# canSlaveV02_8s.net
KiCad netlist of a schematic drawn in EAGLE
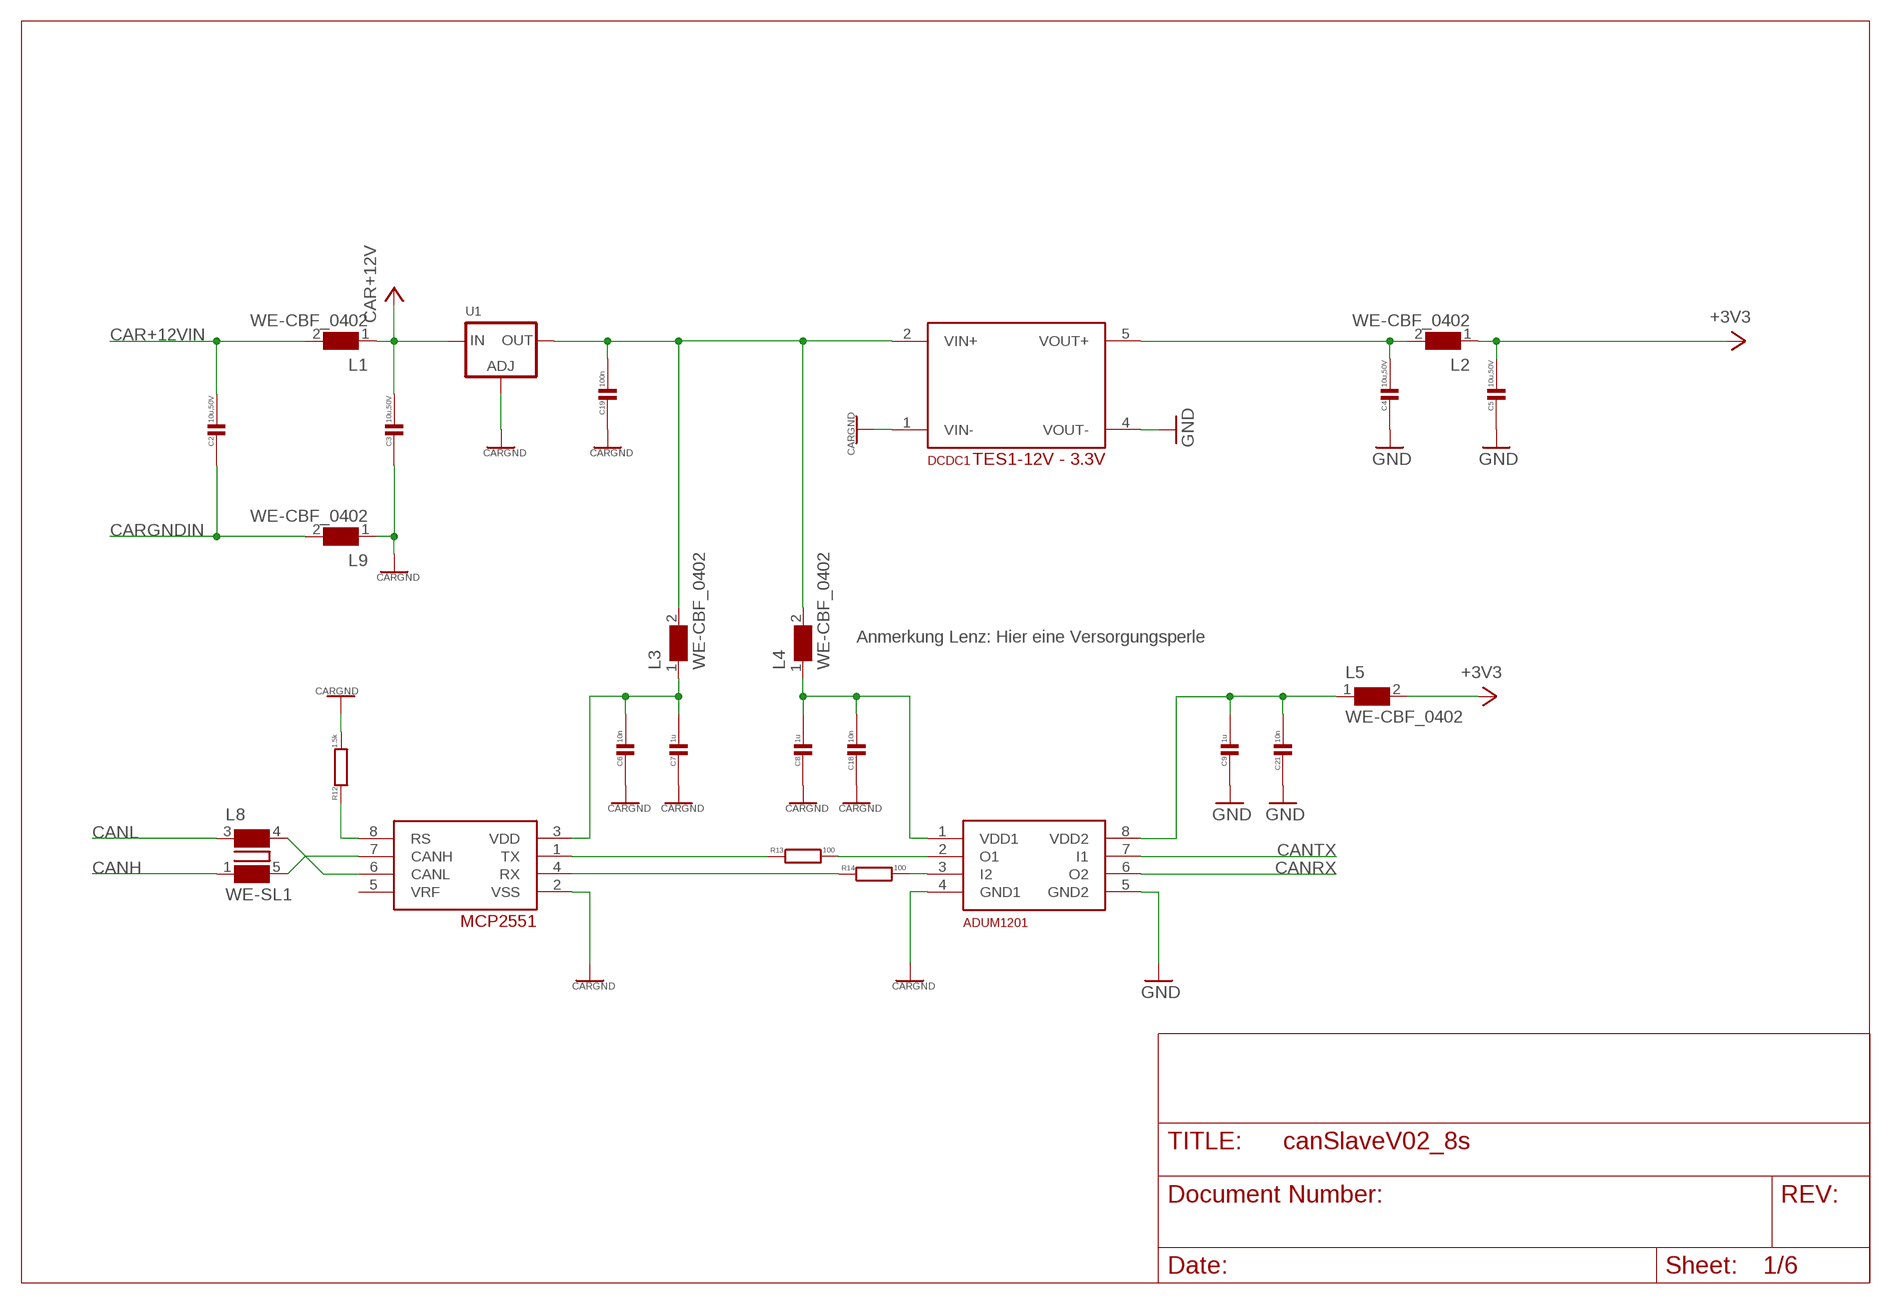
[diagram p0: schematic, sheet 1]
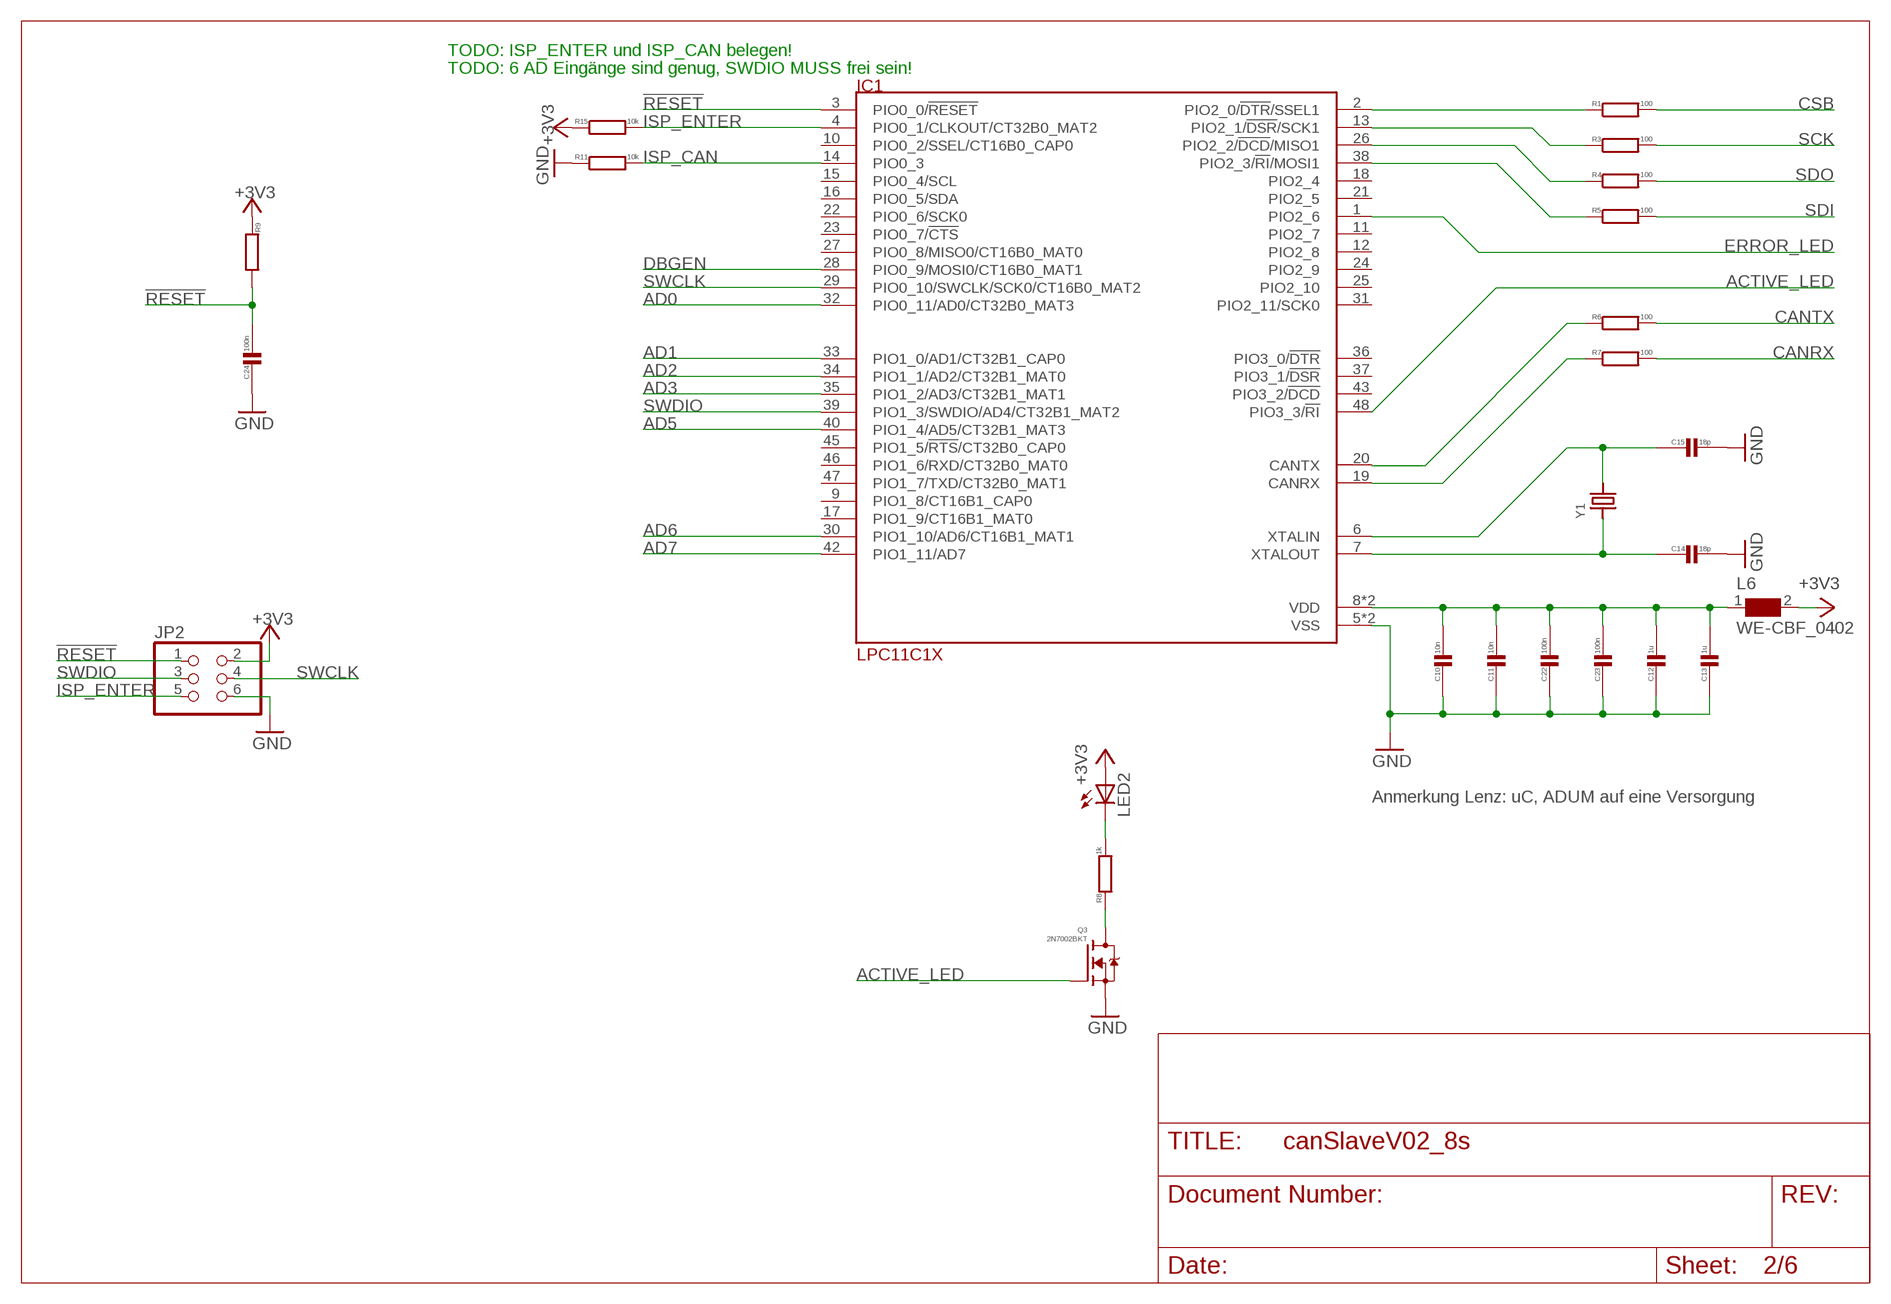
[diagram p1: schematic, sheet 2]
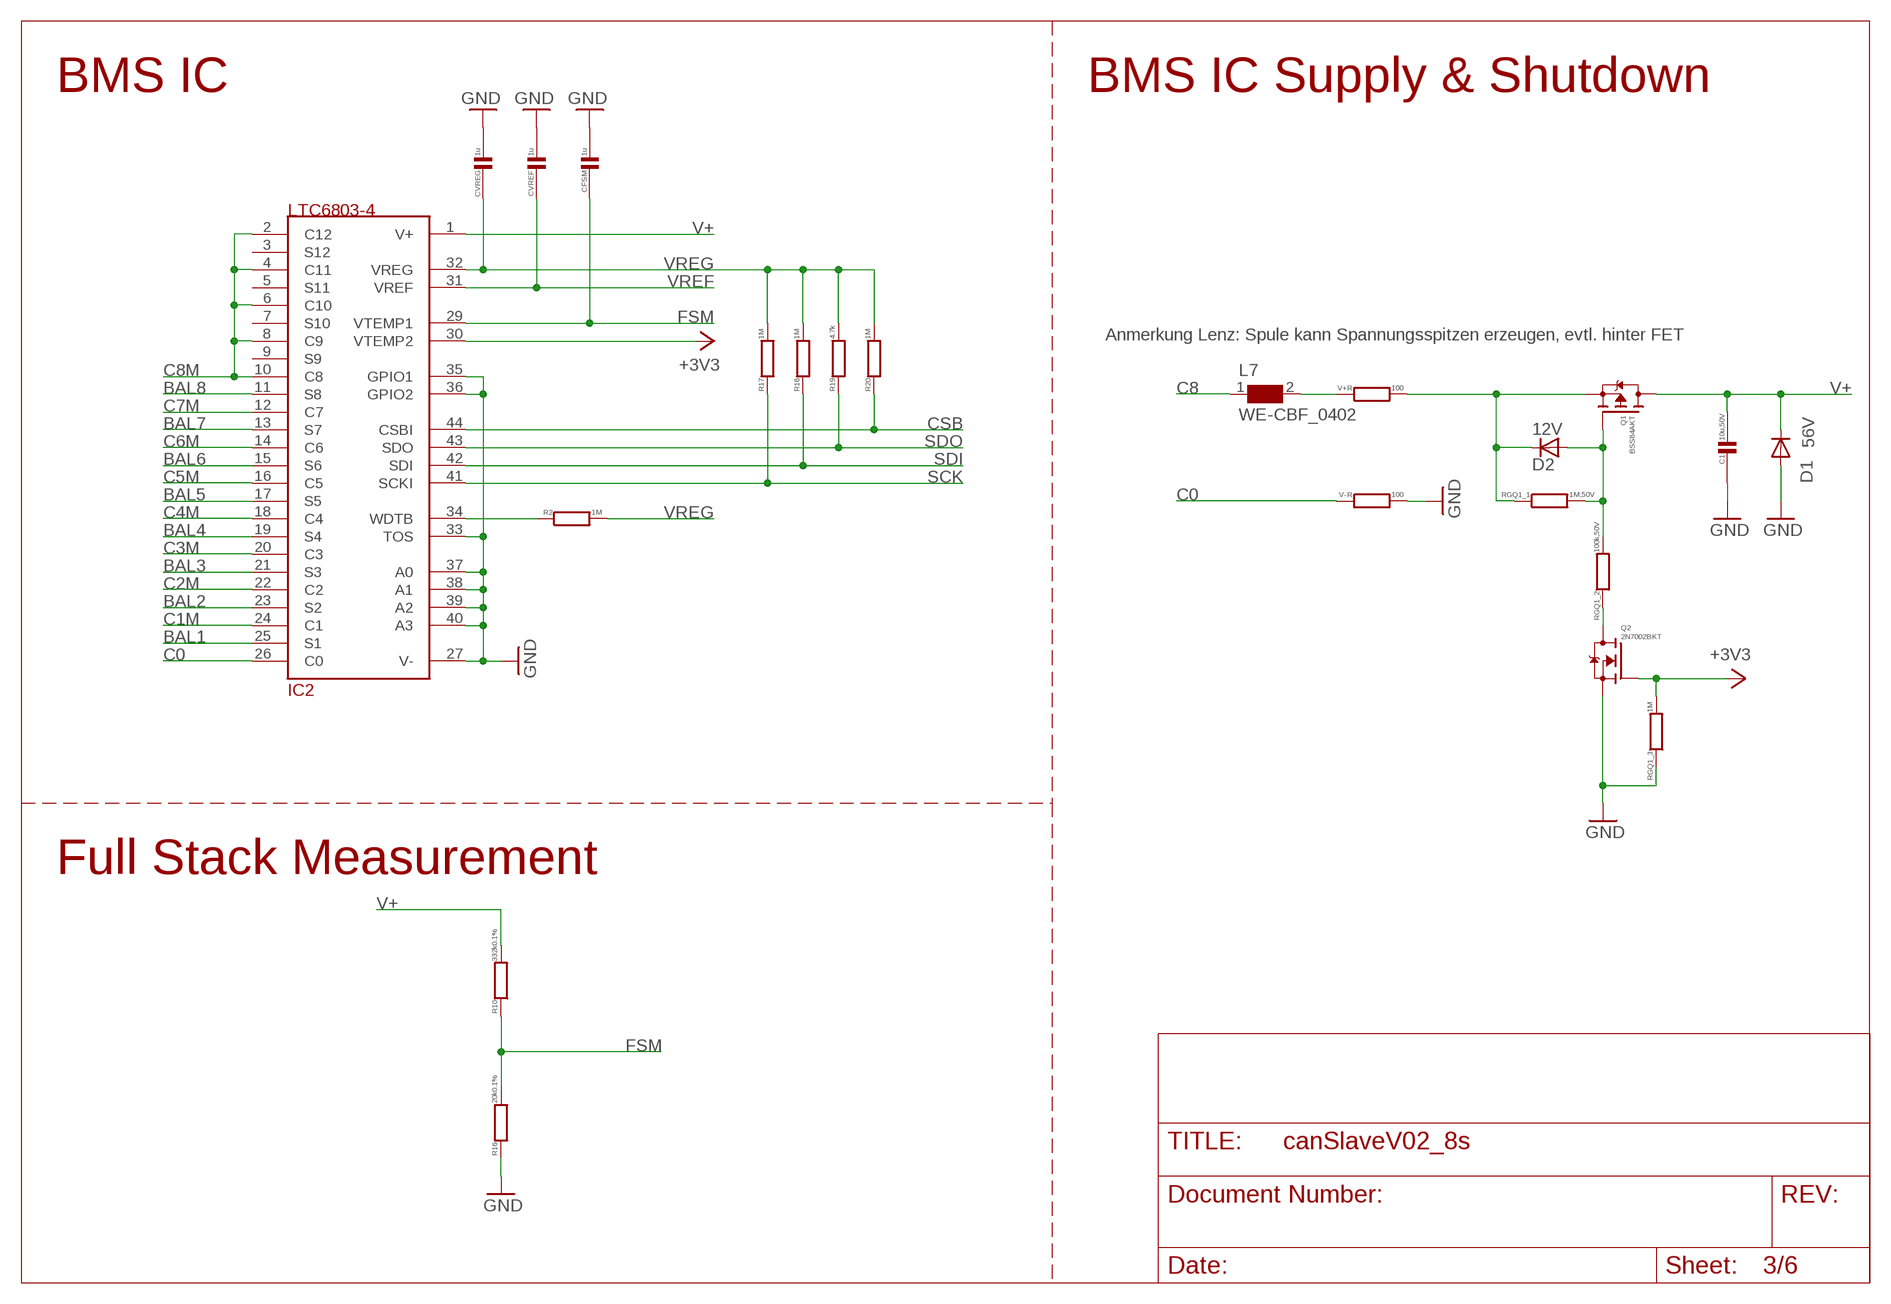
[diagram p2: schematic, sheet 3]
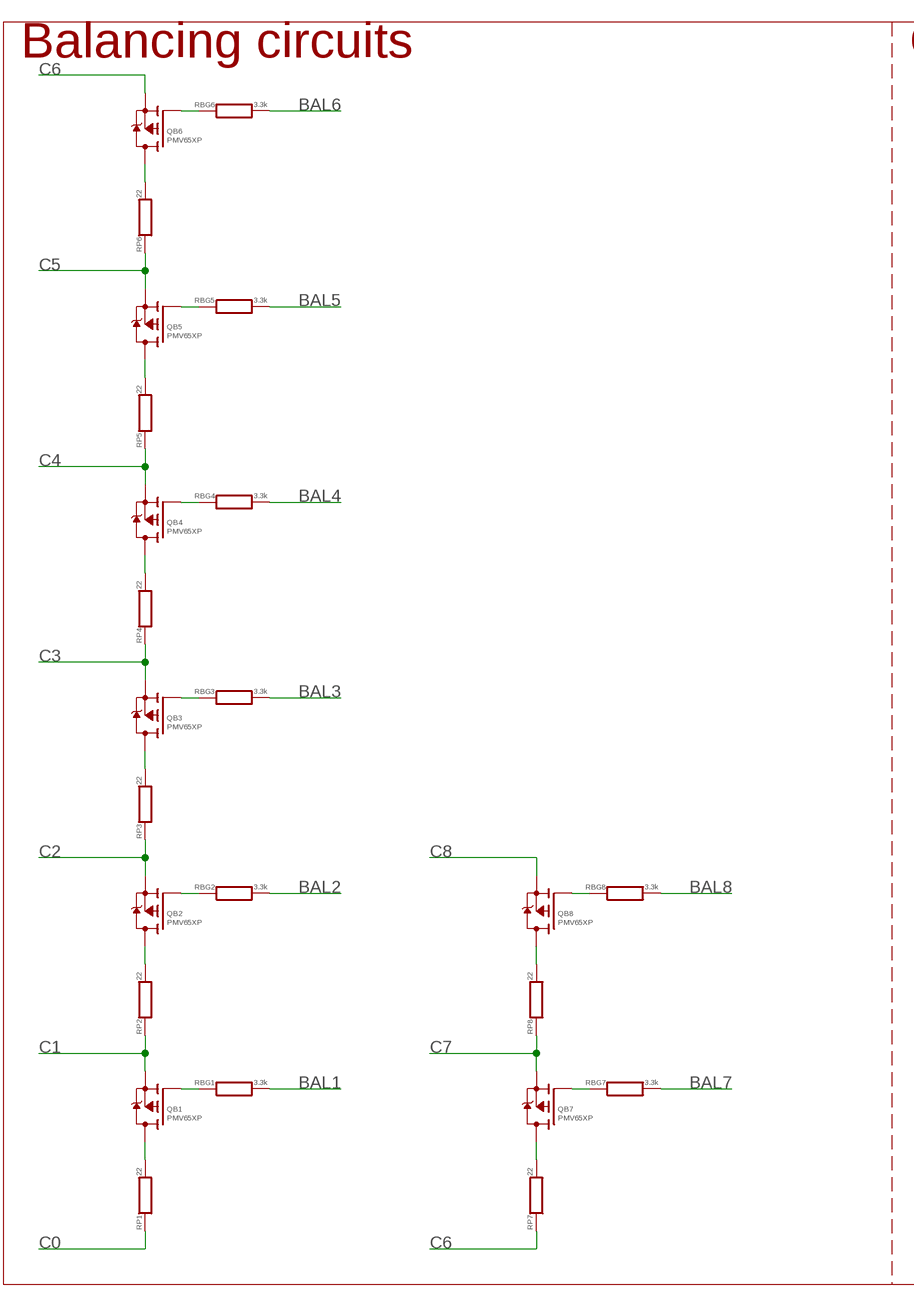
[diagram p3: schematic, sheet 4, part 1 of 2]
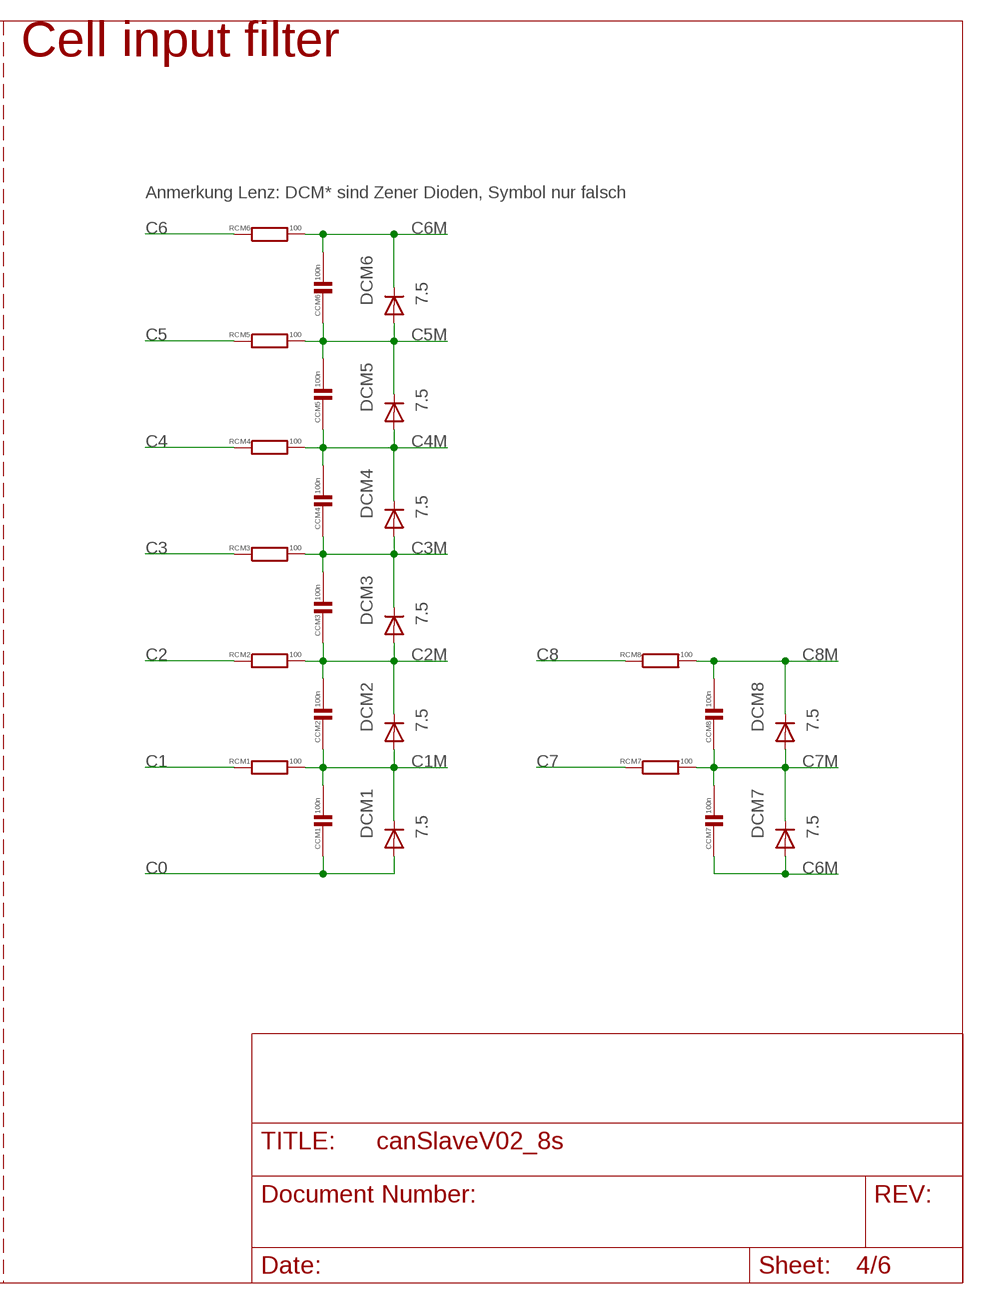
[diagram p4: schematic, sheet 4, part 2 of 2]
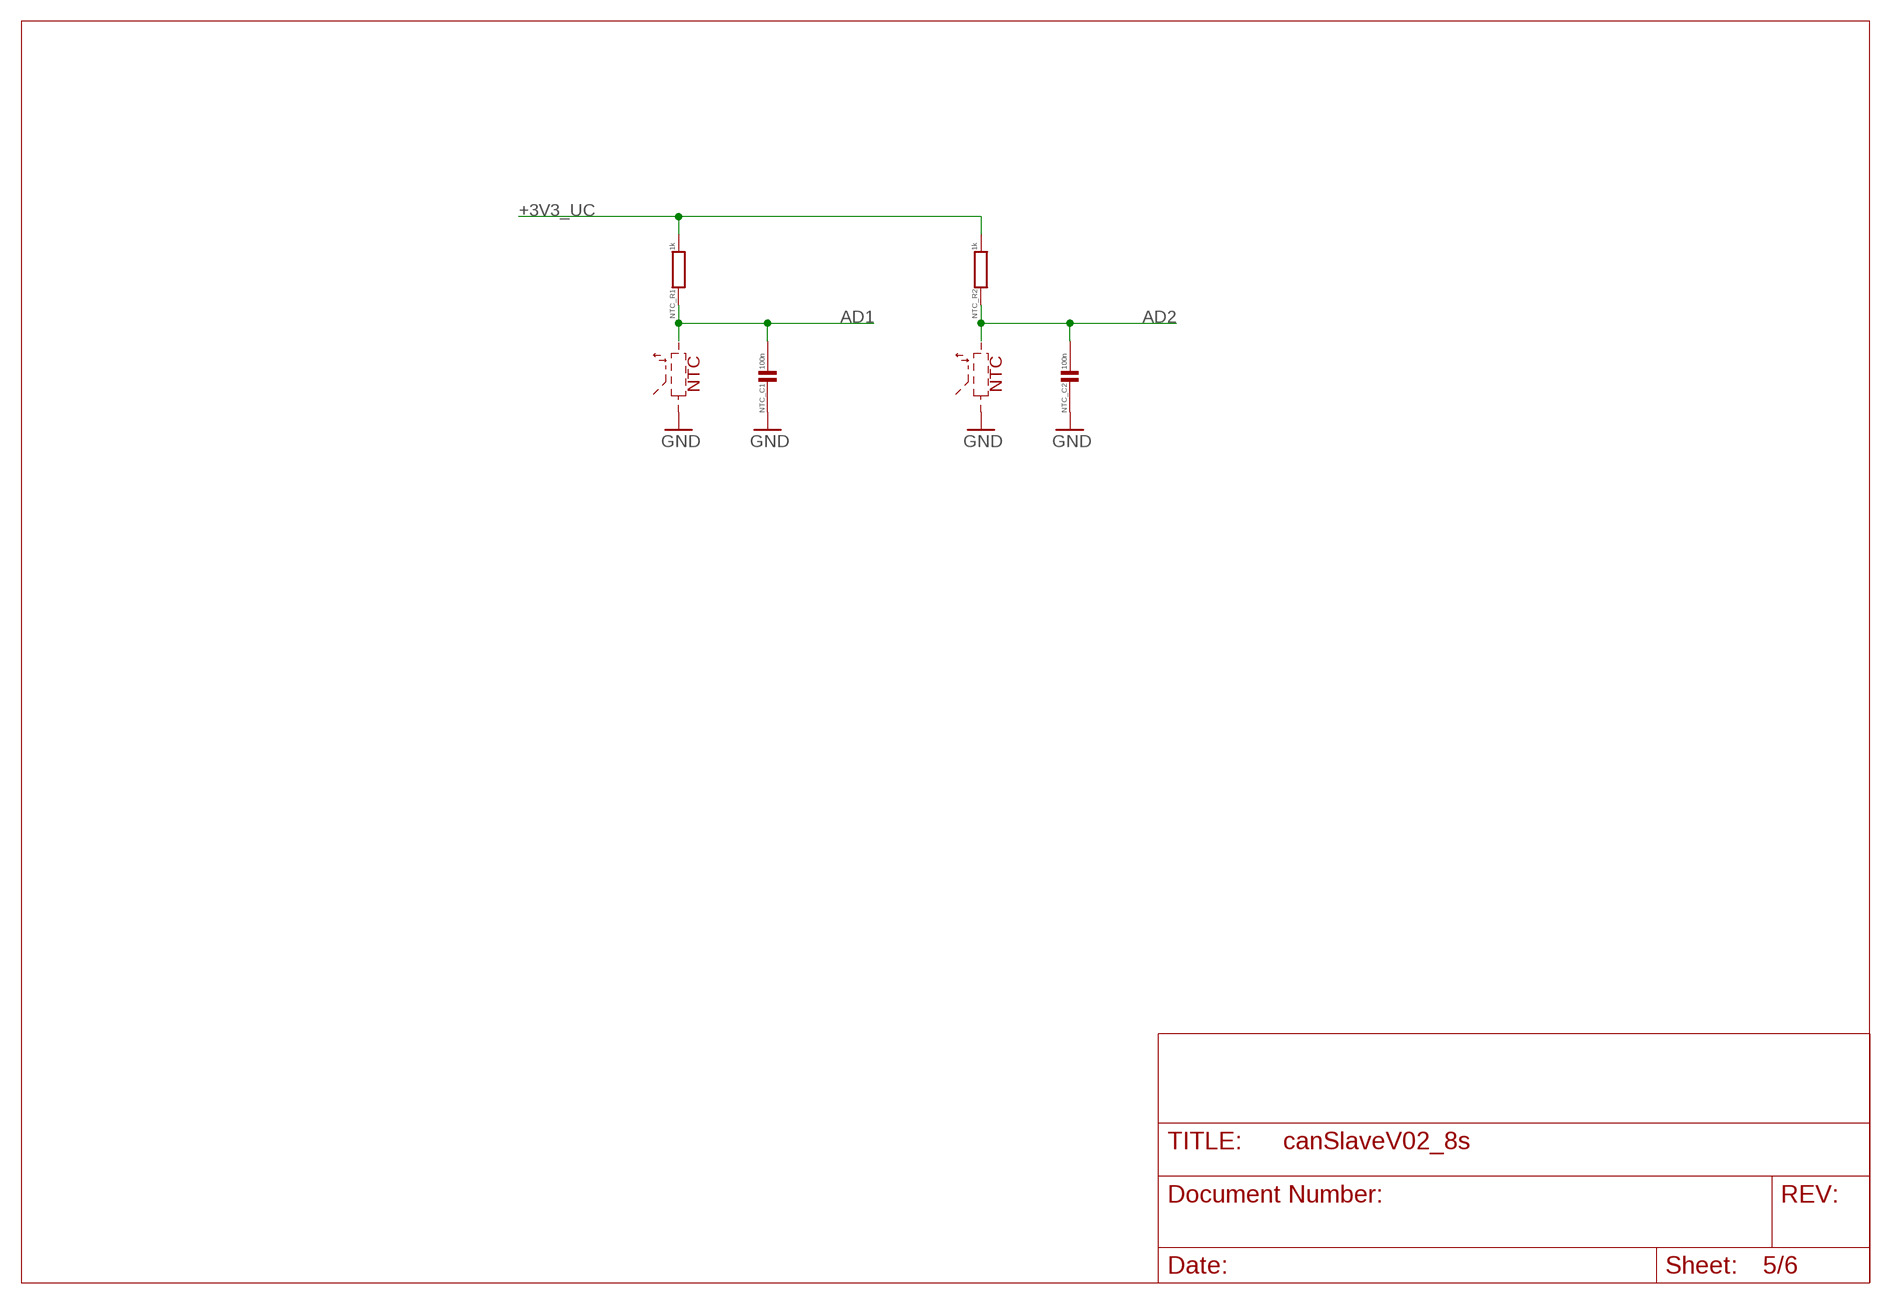
[diagram p5: schematic, sheet 5]
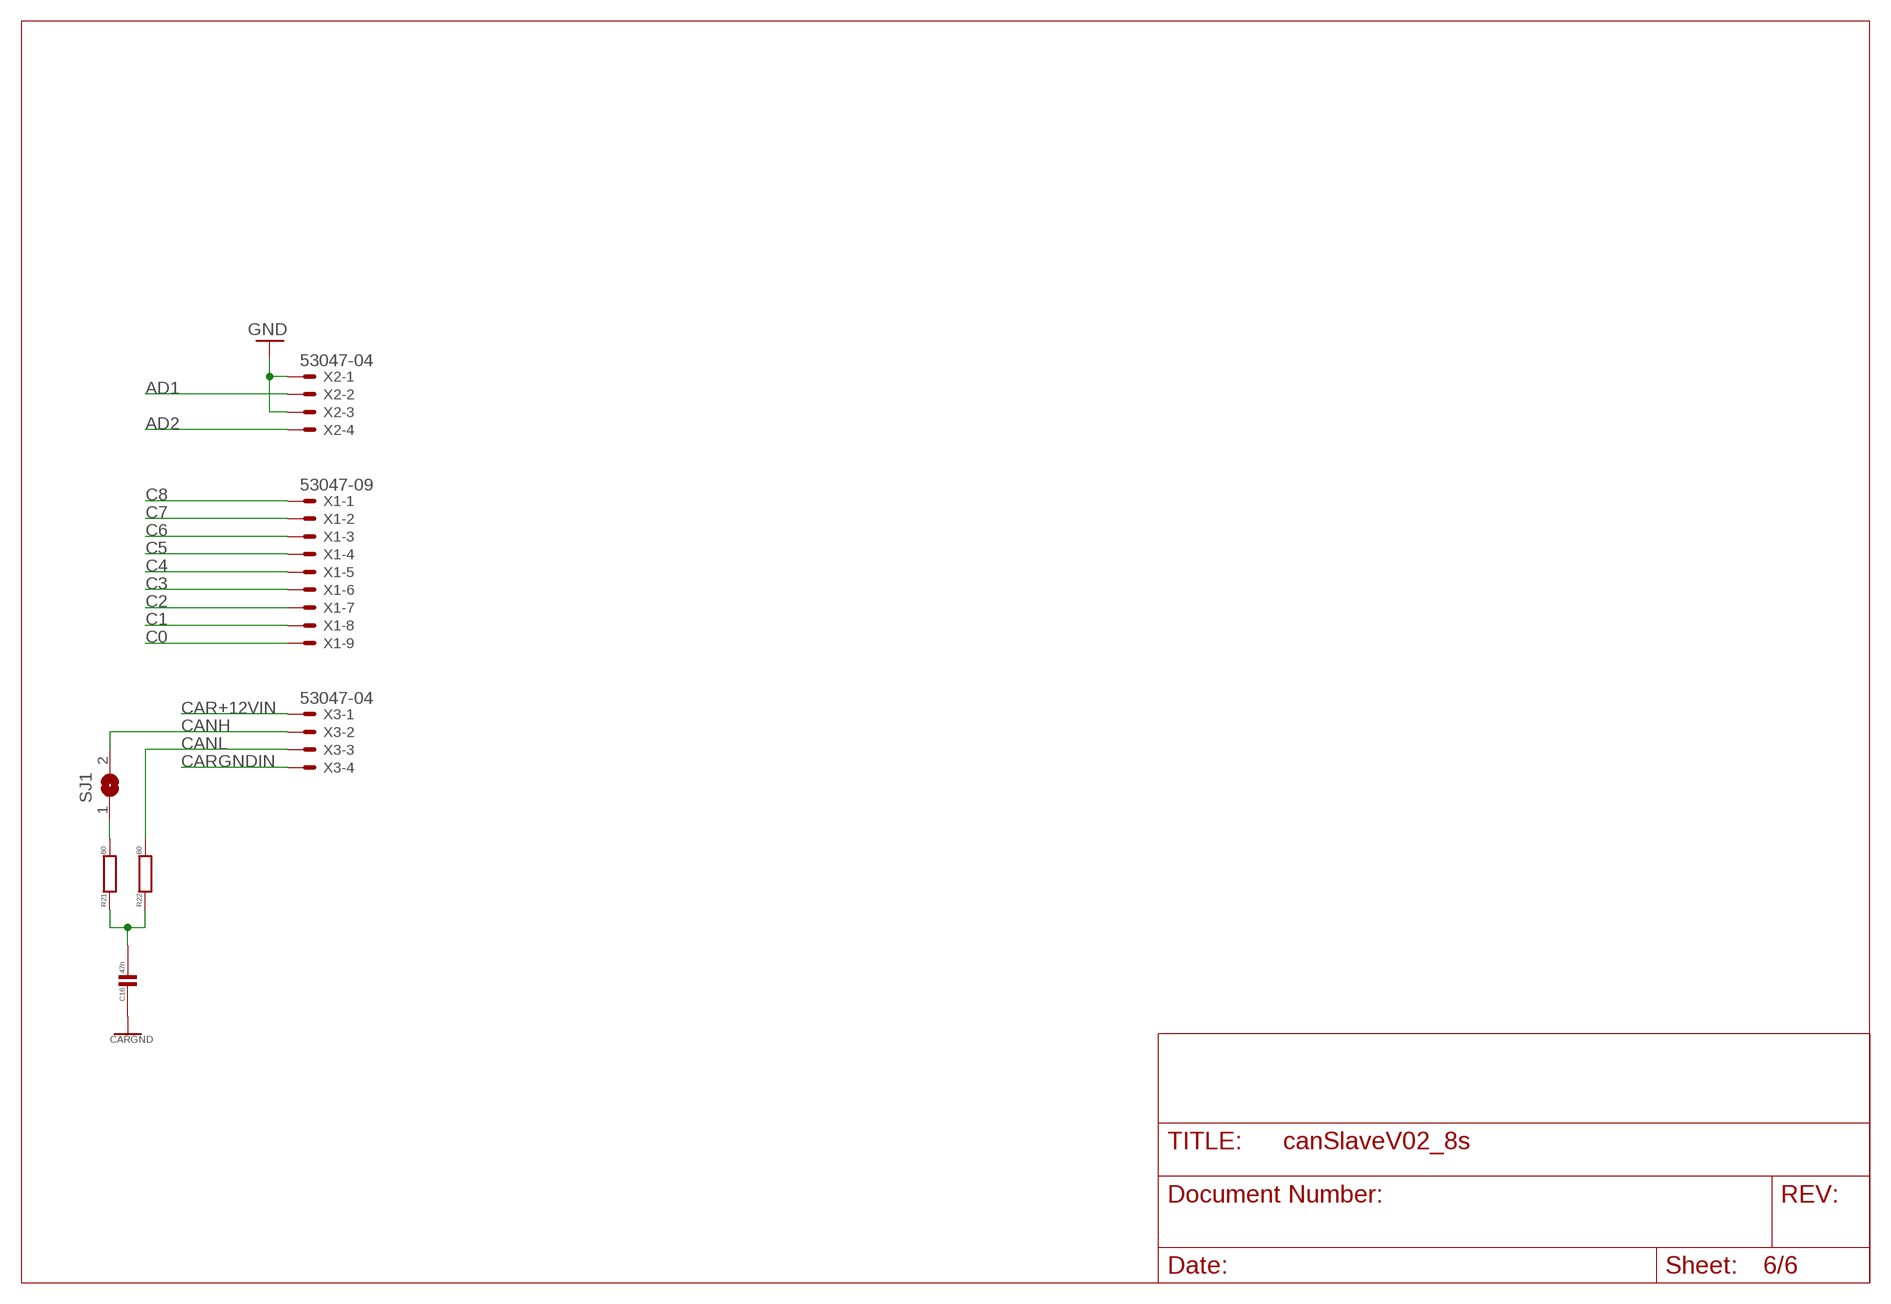
[diagram p6: schematic, sheet 6]

(export (version "E")
  (design (tool "Eeschema 10.0.6"))
  (components
    (comp (ref "C2")
      (value "10u,50V")
      (footprint "eagle-import:C0603")
      (libsource (lib "eagle-import") (part "C0603"))
    )
    (comp (ref "C3")
      (value "10u,50V")
      (footprint "eagle-import:C0603")
      (libsource (lib "eagle-import") (part "C0603"))
    )
    (comp (ref "C4")
      (value "10u,50V")
      (footprint "eagle-import:C0603")
      (libsource (lib "eagle-import") (part "C0603"))
    )
    (comp (ref "C5")
      (value "10u,50V")
      (footprint "eagle-import:C0603")
      (libsource (lib "eagle-import") (part "C0603"))
    )
    (comp (ref "C6")
      (value "10n")
      (footprint "eagle-import:C0402")
      (libsource (lib "eagle-import") (part "C0402"))
    )
    (comp (ref "C7")
      (value "1u")
      (footprint "eagle-import:C0402")
      (libsource (lib "eagle-import") (part "C0402"))
    )
    (comp (ref "C8")
      (value "1u")
      (footprint "eagle-import:C0402")
      (libsource (lib "eagle-import") (part "C0402"))
    )
    (comp (ref "C9")
      (value "1u")
      (footprint "eagle-import:C0402")
      (libsource (lib "eagle-import") (part "C0402"))
    )
    (comp (ref "C18")
      (value "10n")
      (footprint "eagle-import:C0402")
      (libsource (lib "eagle-import") (part "C0402"))
    )
    (comp (ref "C19")
      (value "100n")
      (footprint "eagle-import:C0402")
      (libsource (lib "eagle-import") (part "C0402"))
    )
    (comp (ref "C21")
      (value "10n")
      (footprint "eagle-import:C0402")
      (libsource (lib "eagle-import") (part "C0402"))
    )
    (comp (ref "DCDC1")
      (value "TES1-12V - 3.3V")
      (footprint "eagle-import:ISF")
      (libsource (lib "eagle-import") (part "ISFXXXXA"))
    )
    (comp (ref "IC3")
      (value "ADUM1201")
      (footprint "eagle-import:SO-8")
      (libsource (lib "eagle-import") (part "ADUM1201"))
    )
    (comp (ref "IC4")
      (value "MCP2551")
      (footprint "eagle-import:SO-8")
      (libsource (lib "eagle-import") (part "MCP2551"))
    )
    (comp (ref "L1")
      (value "WE-CBF_0402")
      (footprint "eagle-import:0402")
      (libsource (lib "eagle-import") (part "WE-CBF_0402"))
    )
    (comp (ref "L2")
      (value "WE-CBF_0402")
      (footprint "eagle-import:0402")
      (libsource (lib "eagle-import") (part "WE-CBF_0402"))
    )
    (comp (ref "L3")
      (value "WE-CBF_0402")
      (footprint "eagle-import:0402")
      (libsource (lib "eagle-import") (part "WE-CBF_0402"))
    )
    (comp (ref "L4")
      (value "WE-CBF_0402")
      (footprint "eagle-import:0402")
      (libsource (lib "eagle-import") (part "WE-CBF_0402"))
    )
    (comp (ref "L5")
      (value "WE-CBF_0402")
      (footprint "eagle-import:0402")
      (libsource (lib "eagle-import") (part "WE-CBF_0402"))
    )
    (comp (ref "L8")
      (value "WE-SL1")
      (footprint "eagle-import:WE-SL1")
      (libsource (lib "eagle-import") (part "WE-SL1"))
    )
    (comp (ref "L9")
      (value "WE-CBF_0402")
      (footprint "eagle-import:0402")
      (libsource (lib "eagle-import") (part "WE-CBF_0402"))
    )
    (comp (ref "R12")
      (value "1.5k")
      (footprint "eagle-import:R0402")
      (libsource (lib "eagle-import") (part "R0402"))
    )
    (comp (ref "R13")
      (value "100")
      (footprint "eagle-import:R0402")
      (libsource (lib "eagle-import") (part "R0402"))
    )
    (comp (ref "R14")
      (value "100")
      (footprint "eagle-import:R0402")
      (libsource (lib "eagle-import") (part "R0402"))
    )
    (comp (ref "U1")
      (value "LM1117SOT223-REFLOW")
      (footprint "eagle-import:SOT223-R")
      (libsource (lib "eagle-import") (part "LM1117SOT223-REFLOW"))
    )
    (comp (ref "C16")
      (value "47n")
      (footprint "eagle-import:C0402")
      (libsource (lib "eagle-import") (part "C0402"))
    )
    (comp (ref "R21")
      (value "60")
      (footprint "eagle-import:R0402")
      (libsource (lib "eagle-import") (part "R0402"))
    )
    (comp (ref "R22")
      (value "60")
      (footprint "eagle-import:R0402")
      (libsource (lib "eagle-import") (part "R0402"))
    )
    (comp (ref "SJ1")
      (value "SOLDERJUMPERSMALL")
      (footprint "eagle-import:SOLDERJUMPER_REFLOW_NOPASTE_SMALL")
      (libsource (lib "eagle-import") (part "SOLDERJUMPERSMALL"))
    )
    (comp (ref "X1")
      (value "53047-09")
      (footprint "eagle-import:53047-09")
      (fields
        (field (name "MPN") "53047-0910")
        (field (name "MPN_1") "53047-0910")
        (field (name "OC_FARNELL") "9732888")
        (field (name "OC_NEWARK") "98K9827")
      )
      (libsource (lib "eagle-import") (part "53?-09047"))
    )
    (comp (ref "X2")
      (value "53047-04")
      (footprint "eagle-import:53047-04")
      (fields
        (field (name "MF") "WALDOM/MOLEX")
        (field (name "MPN") "53047-0410")
        (field (name "MF_1") "WALDOM/MOLEX")
        (field (name "MPN_1") "53047-0410")
        (field (name "OC_FARNELL") "9733060")
        (field (name "OC_NEWARK") "38C9900")
      )
      (libsource (lib "eagle-import") (part "53?-04047"))
    )
    (comp (ref "X3")
      (value "53047-04")
      (footprint "eagle-import:53047-04")
      (fields
        (field (name "MF") "WALDOM/MOLEX")
        (field (name "MPN") "53047-0410")
        (field (name "MF_1") "WALDOM/MOLEX")
        (field (name "MPN_1") "53047-0410")
        (field (name "OC_FARNELL") "9733060")
        (field (name "OC_NEWARK") "38C9900")
      )
      (libsource (lib "eagle-import") (part "53?-04047"))
    )
    (comp (ref "C1")
      (value "10u,50V")
      (footprint "eagle-import:C1206")
      (libsource (lib "eagle-import") (part "C1206"))
    )
    (comp (ref "CFSM")
      (value "1u")
      (footprint "eagle-import:C0402")
      (libsource (lib "eagle-import") (part "C0402"))
    )
    (comp (ref "CVREF")
      (value "1u")
      (footprint "eagle-import:C0402")
      (libsource (lib "eagle-import") (part "C0402"))
    )
    (comp (ref "CVREG")
      (value "1u")
      (footprint "eagle-import:C0402")
      (libsource (lib "eagle-import") (part "C0402"))
    )
    (comp (ref "D1")
      (value "56V")
      (footprint "eagle-import:SOD323-R")
      (libsource (lib "eagle-import") (part "DIODE-SOD323-R"))
    )
    (comp (ref "D2")
      (value "12V")
      (footprint "eagle-import:SOD323-R")
      (libsource (lib "eagle-import") (part "DIODE-SOD323-R"))
    )
    (comp (ref "IC2")
      (value "LTC6803-4")
      (footprint "eagle-import:44SSOP")
      (libsource (lib "eagle-import") (part "LTC6803-4"))
    )
    (comp (ref "L7")
      (value "WE-CBF_0402")
      (footprint "eagle-import:0402")
      (libsource (lib "eagle-import") (part "WE-CBF_0402"))
    )
    (comp (ref "Q1")
      (value "BSS84AKT")
      (footprint "eagle-import:SOT416")
      (libsource (lib "eagle-import") (part "BSS84AKT"))
    )
    (comp (ref "Q2")
      (value "2N7002BKT")
      (footprint "eagle-import:SOT416")
      (libsource (lib "eagle-import") (part "2N7002BKT"))
    )
    (comp (ref "R2")
      (value "1M")
      (footprint "eagle-import:R0402")
      (libsource (lib "eagle-import") (part "R0402"))
    )
    (comp (ref "R10")
      (value "332k0.1%")
      (footprint "eagle-import:R0603")
      (libsource (lib "eagle-import") (part "R0603"))
    )
    (comp (ref "R16")
      (value "20k0.1%")
      (footprint "eagle-import:R0603")
      (libsource (lib "eagle-import") (part "R0603"))
    )
    (comp (ref "R17")
      (value "1M")
      (footprint "eagle-import:R0402")
      (libsource (lib "eagle-import") (part "R0402"))
    )
    (comp (ref "R18")
      (value "1M")
      (footprint "eagle-import:R0402")
      (libsource (lib "eagle-import") (part "R0402"))
    )
    (comp (ref "R19")
      (value "4.7k")
      (footprint "eagle-import:R0402")
      (libsource (lib "eagle-import") (part "R0402"))
    )
    (comp (ref "R20")
      (value "1M")
      (footprint "eagle-import:R0402")
      (libsource (lib "eagle-import") (part "R0402"))
    )
    (comp (ref "RGQ1_1")
      (value "1M,50V")
      (footprint "eagle-import:R0603")
      (libsource (lib "eagle-import") (part "R0603"))
    )
    (comp (ref "RGQ1_2")
      (value "100k,50V")
      (footprint "eagle-import:R0603")
      (libsource (lib "eagle-import") (part "R0603"))
    )
    (comp (ref "RGQ1_3")
      (value "1M")
      (footprint "eagle-import:R0402")
      (libsource (lib "eagle-import") (part "R0402"))
    )
    (comp (ref "V+R")
      (value "100")
      (footprint "eagle-import:R0402")
      (libsource (lib "eagle-import") (part "R0402"))
    )
    (comp (ref "V-R")
      (value "100")
      (footprint "eagle-import:R0402")
      (libsource (lib "eagle-import") (part "R0402"))
    )
    (comp (ref "C10")
      (value "10n")
      (footprint "eagle-import:C0402")
      (libsource (lib "eagle-import") (part "C0402"))
    )
    (comp (ref "C11")
      (value "10n")
      (footprint "eagle-import:C0402")
      (libsource (lib "eagle-import") (part "C0402"))
    )
    (comp (ref "C12")
      (value "1u")
      (footprint "eagle-import:C0402")
      (libsource (lib "eagle-import") (part "C0402"))
    )
    (comp (ref "C13")
      (value "1u")
      (footprint "eagle-import:C0402")
      (libsource (lib "eagle-import") (part "C0402"))
    )
    (comp (ref "C14")
      (value "18p")
      (footprint "eagle-import:C0402")
      (libsource (lib "eagle-import") (part "C0402"))
    )
    (comp (ref "C15")
      (value "18p")
      (footprint "eagle-import:C0402")
      (libsource (lib "eagle-import") (part "C0402"))
    )
    (comp (ref "C22")
      (value "100n")
      (footprint "eagle-import:C0402")
      (libsource (lib "eagle-import") (part "C0402"))
    )
    (comp (ref "C23")
      (value "100n")
      (footprint "eagle-import:C0402")
      (libsource (lib "eagle-import") (part "C0402"))
    )
    (comp (ref "C24")
      (value "100n")
      (footprint "eagle-import:C0402")
      (libsource (lib "eagle-import") (part "C0402"))
    )
    (comp (ref "IC1")
      (value "LPC11C1X")
      (footprint "eagle-import:LQFP48")
      (libsource (lib "eagle-import") (part "LPC11C1X"))
    )
    (comp (ref "JP2")
      (value "HEADER-2X31.27")
      (footprint "eagle-import:2X03_1.27MM_SMT")
      (libsource (lib "eagle-import") (part "HEADER-2X31.27"))
    )
    (comp (ref "L6")
      (value "WE-CBF_0402")
      (footprint "eagle-import:0402")
      (libsource (lib "eagle-import") (part "WE-CBF_0402"))
    )
    (comp (ref "LED2")
      (value "LEDCHIP-LED0603")
      (footprint "eagle-import:CHIP-LED0603")
      (libsource (lib "eagle-import") (part "LEDCHIP-LED0603"))
    )
    (comp (ref "Q3")
      (value "2N7002BKT")
      (footprint "eagle-import:SOT416")
      (libsource (lib "eagle-import") (part "2N7002BKT"))
    )
    (comp (ref "R1")
      (value "100")
      (footprint "eagle-import:R0402")
      (libsource (lib "eagle-import") (part "R0402"))
    )
    (comp (ref "R3")
      (value "100")
      (footprint "eagle-import:R0402")
      (libsource (lib "eagle-import") (part "R0402"))
    )
    (comp (ref "R4")
      (value "100")
      (footprint "eagle-import:R0402")
      (libsource (lib "eagle-import") (part "R0402"))
    )
    (comp (ref "R5")
      (value "100")
      (footprint "eagle-import:R0402")
      (libsource (lib "eagle-import") (part "R0402"))
    )
    (comp (ref "R6")
      (value "100")
      (footprint "eagle-import:R0402")
      (libsource (lib "eagle-import") (part "R0402"))
    )
    (comp (ref "R7")
      (value "100")
      (footprint "eagle-import:R0402")
      (libsource (lib "eagle-import") (part "R0402"))
    )
    (comp (ref "R8")
      (value "1k")
      (footprint "eagle-import:R0402")
      (libsource (lib "eagle-import") (part "R0402"))
    )
    (comp (ref "R9")
      (value "R0402")
      (footprint "eagle-import:R0402")
      (libsource (lib "eagle-import") (part "R0402"))
    )
    (comp (ref "R11")
      (value "10k")
      (footprint "eagle-import:R0402")
      (libsource (lib "eagle-import") (part "R0402"))
    )
    (comp (ref "R15")
      (value "10k")
      (footprint "eagle-import:R0402")
      (libsource (lib "eagle-import") (part "R0402"))
    )
    (comp (ref "Y1")
      (value "CRYSTALTHIN")
      (footprint "eagle-import:CRYSTAL_3.2X2.5")
      (libsource (lib "eagle-import") (part "CRYSTALTHIN"))
    )
    (comp (ref "CCM1")
      (value "100n")
      (footprint "eagle-import:C0402")
      (libsource (lib "eagle-import") (part "C0402"))
    )
    (comp (ref "CCM2")
      (value "100n")
      (footprint "eagle-import:C0402")
      (libsource (lib "eagle-import") (part "C0402"))
    )
    (comp (ref "CCM3")
      (value "100n")
      (footprint "eagle-import:C0402")
      (libsource (lib "eagle-import") (part "C0402"))
    )
    (comp (ref "CCM4")
      (value "100n")
      (footprint "eagle-import:C0402")
      (libsource (lib "eagle-import") (part "C0402"))
    )
    (comp (ref "CCM5")
      (value "100n")
      (footprint "eagle-import:C0402")
      (libsource (lib "eagle-import") (part "C0402"))
    )
    (comp (ref "CCM6")
      (value "100n")
      (footprint "eagle-import:C0402")
      (libsource (lib "eagle-import") (part "C0402"))
    )
    (comp (ref "CCM7")
      (value "100n")
      (footprint "eagle-import:C0402")
      (libsource (lib "eagle-import") (part "C0402"))
    )
    (comp (ref "CCM8")
      (value "100n")
      (footprint "eagle-import:C0402")
      (libsource (lib "eagle-import") (part "C0402"))
    )
    (comp (ref "DCM1")
      (value "7.5")
      (footprint "eagle-import:SOD323-R")
      (libsource (lib "eagle-import") (part "DIODE-SOD323-R"))
    )
    (comp (ref "DCM2")
      (value "7.5")
      (footprint "eagle-import:SOD323-R")
      (libsource (lib "eagle-import") (part "DIODE-SOD323-R"))
    )
    (comp (ref "DCM3")
      (value "7.5")
      (footprint "eagle-import:SOD323-R")
      (libsource (lib "eagle-import") (part "DIODE-SOD323-R"))
    )
    (comp (ref "DCM4")
      (value "7.5")
      (footprint "eagle-import:SOD323-R")
      (libsource (lib "eagle-import") (part "DIODE-SOD323-R"))
    )
    (comp (ref "DCM5")
      (value "7.5")
      (footprint "eagle-import:SOD323-R")
      (libsource (lib "eagle-import") (part "DIODE-SOD323-R"))
    )
    (comp (ref "DCM6")
      (value "7.5")
      (footprint "eagle-import:SOD323-R")
      (libsource (lib "eagle-import") (part "DIODE-SOD323-R"))
    )
    (comp (ref "DCM7")
      (value "7.5")
      (footprint "eagle-import:SOD323-R")
      (libsource (lib "eagle-import") (part "DIODE-SOD323-R"))
    )
    (comp (ref "DCM8")
      (value "7.5")
      (footprint "eagle-import:SOD323-R")
      (libsource (lib "eagle-import") (part "DIODE-SOD323-R"))
    )
    (comp (ref "QB1")
      (value "PMV65XP")
      (footprint "eagle-import:SOT416")
      (libsource (lib "eagle-import") (part "BSS84AKT"))
    )
    (comp (ref "QB2")
      (value "PMV65XP")
      (footprint "eagle-import:SOT416")
      (libsource (lib "eagle-import") (part "BSS84AKT"))
    )
    (comp (ref "QB3")
      (value "PMV65XP")
      (footprint "eagle-import:SOT416")
      (libsource (lib "eagle-import") (part "BSS84AKT"))
    )
    (comp (ref "QB4")
      (value "PMV65XP")
      (footprint "eagle-import:SOT416")
      (libsource (lib "eagle-import") (part "BSS84AKT"))
    )
    (comp (ref "QB5")
      (value "PMV65XP")
      (footprint "eagle-import:SOT416")
      (libsource (lib "eagle-import") (part "BSS84AKT"))
    )
    (comp (ref "QB6")
      (value "PMV65XP")
      (footprint "eagle-import:SOT416")
      (libsource (lib "eagle-import") (part "BSS84AKT"))
    )
    (comp (ref "QB7")
      (value "PMV65XP")
      (footprint "eagle-import:SOT416")
      (libsource (lib "eagle-import") (part "BSS84AKT"))
    )
    (comp (ref "QB8")
      (value "PMV65XP")
      (footprint "eagle-import:SOT416")
      (libsource (lib "eagle-import") (part "BSS84AKT"))
    )
    (comp (ref "RBG1")
      (value "3.3k")
      (footprint "eagle-import:R0402")
      (libsource (lib "eagle-import") (part "R0402"))
    )
    (comp (ref "RBG2")
      (value "3.3k")
      (footprint "eagle-import:R0402")
      (libsource (lib "eagle-import") (part "R0402"))
    )
    (comp (ref "RBG3")
      (value "3.3k")
      (footprint "eagle-import:R0402")
      (libsource (lib "eagle-import") (part "R0402"))
    )
    (comp (ref "RBG4")
      (value "3.3k")
      (footprint "eagle-import:R0402")
      (libsource (lib "eagle-import") (part "R0402"))
    )
    (comp (ref "RBG5")
      (value "3.3k")
      (footprint "eagle-import:R0402")
      (libsource (lib "eagle-import") (part "R0402"))
    )
    (comp (ref "RBG6")
      (value "3.3k")
      (footprint "eagle-import:R0402")
      (libsource (lib "eagle-import") (part "R0402"))
    )
    (comp (ref "RBG7")
      (value "3.3k")
      (footprint "eagle-import:R0402")
      (libsource (lib "eagle-import") (part "R0402"))
    )
    (comp (ref "RBG8")
      (value "3.3k")
      (footprint "eagle-import:R0402")
      (libsource (lib "eagle-import") (part "R0402"))
    )
    (comp (ref "RCM1")
      (value "100")
      (footprint "eagle-import:R0402")
      (libsource (lib "eagle-import") (part "R0402"))
    )
    (comp (ref "RCM2")
      (value "100")
      (footprint "eagle-import:R0402")
      (libsource (lib "eagle-import") (part "R0402"))
    )
    (comp (ref "RCM3")
      (value "100")
      (footprint "eagle-import:R0402")
      (libsource (lib "eagle-import") (part "R0402"))
    )
    (comp (ref "RCM4")
      (value "100")
      (footprint "eagle-import:R0402")
      (libsource (lib "eagle-import") (part "R0402"))
    )
    (comp (ref "RCM5")
      (value "100")
      (footprint "eagle-import:R0402")
      (libsource (lib "eagle-import") (part "R0402"))
    )
    (comp (ref "RCM6")
      (value "100")
      (footprint "eagle-import:R0402")
      (libsource (lib "eagle-import") (part "R0402"))
    )
    (comp (ref "RCM7")
      (value "100")
      (footprint "eagle-import:R0402")
      (libsource (lib "eagle-import") (part "R0402"))
    )
    (comp (ref "RCM8")
      (value "100")
      (footprint "eagle-import:R0402")
      (libsource (lib "eagle-import") (part "R0402"))
    )
    (comp (ref "RP1")
      (value "22")
      (footprint "eagle-import:R2512")
      (libsource (lib "eagle-import") (part "R2512"))
    )
    (comp (ref "RP2")
      (value "22")
      (footprint "eagle-import:R2512")
      (libsource (lib "eagle-import") (part "R2512"))
    )
    (comp (ref "RP3")
      (value "22")
      (footprint "eagle-import:R2512")
      (libsource (lib "eagle-import") (part "R2512"))
    )
    (comp (ref "RP4")
      (value "22")
      (footprint "eagle-import:R2512")
      (libsource (lib "eagle-import") (part "R2512"))
    )
    (comp (ref "RP5")
      (value "22")
      (footprint "eagle-import:R2512")
      (libsource (lib "eagle-import") (part "R2512"))
    )
    (comp (ref "RP6")
      (value "22")
      (footprint "eagle-import:R2512")
      (libsource (lib "eagle-import") (part "R2512"))
    )
    (comp (ref "RP7")
      (value "22")
      (footprint "eagle-import:R2512")
      (libsource (lib "eagle-import") (part "R2512"))
    )
    (comp (ref "RP8")
      (value "22")
      (footprint "eagle-import:R2512")
      (libsource (lib "eagle-import") (part "R2512"))
    )
    (comp (ref "NTC_C1")
      (value "100n")
      (footprint "eagle-import:C0402")
      (libsource (lib "eagle-import") (part "C0402"))
    )
    (comp (ref "NTC_C2")
      (value "100n")
      (footprint "eagle-import:C0402")
      (libsource (lib "eagle-import") (part "C0402"))
    )
    (comp (ref "NTC_R1")
      (value "1k")
      (footprint "eagle-import:R0402")
      (libsource (lib "eagle-import") (part "R0402"))
    )
    (comp (ref "NTC_R2")
      (value "1k")
      (footprint "eagle-import:R0402")
      (libsource (lib "eagle-import") (part "R0402"))
    )
  )
  (nets
    (net (code "1") (name "+3V3") (class "Default")
      (node (ref "C5") (pin "1") (pinfunction "1_1") (pintype "passive"))
      (node (ref "IC2") (pin "30") (pinfunction "VTEMP2_30") (pintype "bidirectional"))
      (node (ref "JP2") (pin "2") (pinfunction "2_2") (pintype "passive"))
      (node (ref "L2") (pin "1") (pinfunction "1_1") (pintype "passive"))
      (node (ref "L5") (pin "2") (pinfunction "2_2") (pintype "passive"))
      (node (ref "L6") (pin "2") (pinfunction "2_2") (pintype "passive"))
      (node (ref "LED2") (pin "A") (pinfunction "A_A") (pintype "passive"))
      (node (ref "Q2") (pin "1") (pinfunction "G_1") (pintype "passive"))
      (node (ref "R15") (pin "1") (pinfunction "1_1") (pintype "passive"))
      (node (ref "R9") (pin "1") (pinfunction "1_1") (pintype "passive"))
      (node (ref "RGQ1_3") (pin "2") (pinfunction "2_2") (pintype "passive"))
    )
    (net (code "2") (name "+3V3_UC") (class "Default")
      (node (ref "C10") (pin "1") (pinfunction "1_1") (pintype "passive"))
      (node (ref "C11") (pin "1") (pinfunction "1_1") (pintype "passive"))
      (node (ref "C12") (pin "1") (pinfunction "1_1") (pintype "passive"))
      (node (ref "C13") (pin "1") (pinfunction "1_1") (pintype "passive"))
      (node (ref "C22") (pin "1") (pinfunction "1_1") (pintype "passive"))
      (node (ref "C23") (pin "1") (pinfunction "1_1") (pintype "passive"))
      (node (ref "IC1") (pin "44") (pinfunction "VDD_44") (pintype "bidirectional"))
      (node (ref "IC1") (pin "8") (pinfunction "VDD_8") (pintype "bidirectional"))
      (node (ref "L6") (pin "1") (pinfunction "1_1") (pintype "passive"))
      (node (ref "NTC_R1") (pin "2") (pinfunction "2_2") (pintype "passive"))
      (node (ref "NTC_R2") (pin "2") (pinfunction "2_2") (pintype "passive"))
    )
    (net (code "3") (name "ACTIVE_LED") (class "Default")
      (node (ref "IC1") (pin "48") (pinfunction "PIO3_3/~{RI}_48") (pintype "bidirectional"))
      (node (ref "Q3") (pin "1") (pinfunction "G_1") (pintype "passive"))
    )
    (net (code "4") (name "AD0") (class "Default")
      (node (ref "IC1") (pin "32") (pinfunction "PIO0_11/AD0/CT32B0_MAT3_32") (pintype "bidirectional"))
    )
    (net (code "5") (name "AD1") (class "Default")
      (node (ref "IC1") (pin "33") (pinfunction "PIO1_0/AD1/CT32B1_CAP0_33") (pintype "bidirectional"))
      (node (ref "NTC_C1") (pin "1") (pinfunction "1_1") (pintype "passive"))
      (node (ref "NTC_R1") (pin "1") (pinfunction "1_1") (pintype "passive"))
      (node (ref "X2") (pin "2") (pinfunction "S_2") (pintype "passive"))
    )
    (net (code "6") (name "AD2") (class "Default")
      (node (ref "IC1") (pin "34") (pinfunction "PIO1_1/AD2/CT32B1_MAT0_34") (pintype "bidirectional"))
      (node (ref "NTC_C2") (pin "1") (pinfunction "1_1") (pintype "passive"))
      (node (ref "NTC_R2") (pin "1") (pinfunction "1_1") (pintype "passive"))
      (node (ref "X2") (pin "4") (pinfunction "S_4") (pintype "passive"))
    )
    (net (code "7") (name "AD3") (class "Default")
      (node (ref "IC1") (pin "35") (pinfunction "PIO1_2/AD3/CT32B1_MAT1_35") (pintype "bidirectional"))
    )
    (net (code "8") (name "AD5") (class "Default")
      (node (ref "IC1") (pin "40") (pinfunction "PIO1_4/AD5/CT32B1_MAT3_40") (pintype "bidirectional"))
    )
    (net (code "9") (name "AD6") (class "Default")
      (node (ref "IC1") (pin "30") (pinfunction "PIO1_10/AD6/CT16B1_MAT1_30") (pintype "bidirectional"))
    )
    (net (code "10") (name "AD7") (class "Default")
      (node (ref "IC1") (pin "42") (pinfunction "PIO1_11/AD7_42") (pintype "bidirectional"))
    )
    (net (code "11") (name "BAL1") (class "Default")
      (node (ref "IC2") (pin "25") (pinfunction "S1_25") (pintype "bidirectional"))
      (node (ref "RBG1") (pin "2") (pinfunction "2_2") (pintype "passive"))
    )
    (net (code "12") (name "BAL2") (class "Default")
      (node (ref "IC2") (pin "23") (pinfunction "S2_23") (pintype "bidirectional"))
      (node (ref "RBG2") (pin "2") (pinfunction "2_2") (pintype "passive"))
    )
    (net (code "13") (name "BAL3") (class "Default")
      (node (ref "IC2") (pin "21") (pinfunction "S3_21") (pintype "bidirectional"))
      (node (ref "RBG3") (pin "2") (pinfunction "2_2") (pintype "passive"))
    )
    (net (code "14") (name "BAL4") (class "Default")
      (node (ref "IC2") (pin "19") (pinfunction "S4_19") (pintype "bidirectional"))
      (node (ref "RBG4") (pin "2") (pinfunction "2_2") (pintype "passive"))
    )
    (net (code "15") (name "BAL5") (class "Default")
      (node (ref "IC2") (pin "17") (pinfunction "S5_17") (pintype "bidirectional"))
      (node (ref "RBG5") (pin "2") (pinfunction "2_2") (pintype "passive"))
    )
    (net (code "16") (name "BAL6") (class "Default")
      (node (ref "IC2") (pin "15") (pinfunction "S6_15") (pintype "bidirectional"))
      (node (ref "RBG6") (pin "2") (pinfunction "2_2") (pintype "passive"))
    )
    (net (code "17") (name "BAL7") (class "Default")
      (node (ref "IC2") (pin "13") (pinfunction "S7_13") (pintype "bidirectional"))
      (node (ref "RBG7") (pin "2") (pinfunction "2_2") (pintype "passive"))
    )
    (net (code "18") (name "BAL8") (class "Default")
      (node (ref "IC2") (pin "11") (pinfunction "S8_11") (pintype "bidirectional"))
      (node (ref "RBG8") (pin "2") (pinfunction "2_2") (pintype "passive"))
    )
    (net (code "19") (name "C0") (class "Default")
      (node (ref "CCM1") (pin "2") (pinfunction "2_2") (pintype "passive"))
      (node (ref "DCM1") (pin "A") (pinfunction "A_A") (pintype "passive"))
      (node (ref "IC2") (pin "26") (pinfunction "C0_26") (pintype "bidirectional"))
      (node (ref "RP1") (pin "1") (pinfunction "1_1") (pintype "passive"))
      (node (ref "V-R") (pin "1") (pinfunction "1_1") (pintype "passive"))
      (node (ref "X1") (pin "9") (pinfunction "S_9") (pintype "passive"))
    )
    (net (code "20") (name "C1") (class "Default")
      (node (ref "QB1") (pin "2") (pinfunction "S_2") (pintype "passive"))
      (node (ref "RCM1") (pin "1") (pinfunction "1_1") (pintype "passive"))
      (node (ref "RP2") (pin "1") (pinfunction "1_1") (pintype "passive"))
      (node (ref "X1") (pin "8") (pinfunction "S_8") (pintype "passive"))
    )
    (net (code "21") (name "C1M") (class "Default")
      (node (ref "CCM1") (pin "1") (pinfunction "1_1") (pintype "passive"))
      (node (ref "CCM2") (pin "2") (pinfunction "2_2") (pintype "passive"))
      (node (ref "DCM1") (pin "C") (pinfunction "C_C") (pintype "passive"))
      (node (ref "DCM2") (pin "A") (pinfunction "A_A") (pintype "passive"))
      (node (ref "IC2") (pin "24") (pinfunction "C1_24") (pintype "bidirectional"))
      (node (ref "RCM1") (pin "2") (pinfunction "2_2") (pintype "passive"))
    )
    (net (code "22") (name "C2") (class "Default")
      (node (ref "QB2") (pin "2") (pinfunction "S_2") (pintype "passive"))
      (node (ref "RCM2") (pin "1") (pinfunction "1_1") (pintype "passive"))
      (node (ref "RP3") (pin "1") (pinfunction "1_1") (pintype "passive"))
      (node (ref "X1") (pin "7") (pinfunction "S_7") (pintype "passive"))
    )
    (net (code "23") (name "C2M") (class "Default")
      (node (ref "CCM2") (pin "1") (pinfunction "1_1") (pintype "passive"))
      (node (ref "CCM3") (pin "2") (pinfunction "2_2") (pintype "passive"))
      (node (ref "DCM2") (pin "C") (pinfunction "C_C") (pintype "passive"))
      (node (ref "DCM3") (pin "A") (pinfunction "A_A") (pintype "passive"))
      (node (ref "IC2") (pin "22") (pinfunction "C2_22") (pintype "bidirectional"))
      (node (ref "RCM2") (pin "2") (pinfunction "2_2") (pintype "passive"))
    )
    (net (code "24") (name "C3") (class "Default")
      (node (ref "QB3") (pin "2") (pinfunction "S_2") (pintype "passive"))
      (node (ref "RCM3") (pin "1") (pinfunction "1_1") (pintype "passive"))
      (node (ref "RP4") (pin "1") (pinfunction "1_1") (pintype "passive"))
      (node (ref "X1") (pin "6") (pinfunction "S_6") (pintype "passive"))
    )
    (net (code "25") (name "C3M") (class "Default")
      (node (ref "CCM3") (pin "1") (pinfunction "1_1") (pintype "passive"))
      (node (ref "CCM4") (pin "2") (pinfunction "2_2") (pintype "passive"))
      (node (ref "DCM3") (pin "C") (pinfunction "C_C") (pintype "passive"))
      (node (ref "DCM4") (pin "A") (pinfunction "A_A") (pintype "passive"))
      (node (ref "IC2") (pin "20") (pinfunction "C3_20") (pintype "bidirectional"))
      (node (ref "RCM3") (pin "2") (pinfunction "2_2") (pintype "passive"))
    )
    (net (code "26") (name "C4") (class "Default")
      (node (ref "QB4") (pin "2") (pinfunction "S_2") (pintype "passive"))
      (node (ref "RCM4") (pin "1") (pinfunction "1_1") (pintype "passive"))
      (node (ref "RP5") (pin "1") (pinfunction "1_1") (pintype "passive"))
      (node (ref "X1") (pin "5") (pinfunction "S_5") (pintype "passive"))
    )
    (net (code "27") (name "C4M") (class "Default")
      (node (ref "CCM4") (pin "1") (pinfunction "1_1") (pintype "passive"))
      (node (ref "CCM5") (pin "2") (pinfunction "2_2") (pintype "passive"))
      (node (ref "DCM4") (pin "C") (pinfunction "C_C") (pintype "passive"))
      (node (ref "DCM5") (pin "A") (pinfunction "A_A") (pintype "passive"))
      (node (ref "IC2") (pin "18") (pinfunction "C4_18") (pintype "bidirectional"))
      (node (ref "RCM4") (pin "2") (pinfunction "2_2") (pintype "passive"))
    )
    (net (code "28") (name "C5") (class "Default")
      (node (ref "QB5") (pin "2") (pinfunction "S_2") (pintype "passive"))
      (node (ref "RCM5") (pin "1") (pinfunction "1_1") (pintype "passive"))
      (node (ref "RP6") (pin "1") (pinfunction "1_1") (pintype "passive"))
      (node (ref "X1") (pin "4") (pinfunction "S_4") (pintype "passive"))
    )
    (net (code "29") (name "C5M") (class "Default")
      (node (ref "CCM5") (pin "1") (pinfunction "1_1") (pintype "passive"))
      (node (ref "CCM6") (pin "2") (pinfunction "2_2") (pintype "passive"))
      (node (ref "DCM5") (pin "C") (pinfunction "C_C") (pintype "passive"))
      (node (ref "DCM6") (pin "A") (pinfunction "A_A") (pintype "passive"))
      (node (ref "IC2") (pin "16") (pinfunction "C5_16") (pintype "bidirectional"))
      (node (ref "RCM5") (pin "2") (pinfunction "2_2") (pintype "passive"))
    )
    (net (code "30") (name "C6") (class "Default")
      (node (ref "QB6") (pin "2") (pinfunction "S_2") (pintype "passive"))
      (node (ref "RCM6") (pin "1") (pinfunction "1_1") (pintype "passive"))
      (node (ref "RP7") (pin "1") (pinfunction "1_1") (pintype "passive"))
      (node (ref "X1") (pin "3") (pinfunction "S_3") (pintype "passive"))
    )
    (net (code "31") (name "C6M") (class "Default")
      (node (ref "CCM6") (pin "1") (pinfunction "1_1") (pintype "passive"))
      (node (ref "CCM7") (pin "2") (pinfunction "2_2") (pintype "passive"))
      (node (ref "DCM6") (pin "C") (pinfunction "C_C") (pintype "passive"))
      (node (ref "DCM7") (pin "A") (pinfunction "A_A") (pintype "passive"))
      (node (ref "IC2") (pin "14") (pinfunction "C6_14") (pintype "bidirectional"))
      (node (ref "RCM6") (pin "2") (pinfunction "2_2") (pintype "passive"))
    )
    (net (code "32") (name "C7") (class "Default")
      (node (ref "QB7") (pin "2") (pinfunction "S_2") (pintype "passive"))
      (node (ref "RCM7") (pin "1") (pinfunction "1_1") (pintype "passive"))
      (node (ref "RP8") (pin "1") (pinfunction "1_1") (pintype "passive"))
      (node (ref "X1") (pin "2") (pinfunction "S_2") (pintype "passive"))
    )
    (net (code "33") (name "C7M") (class "Default")
      (node (ref "CCM7") (pin "1") (pinfunction "1_1") (pintype "passive"))
      (node (ref "CCM8") (pin "2") (pinfunction "2_2") (pintype "passive"))
      (node (ref "DCM7") (pin "C") (pinfunction "C_C") (pintype "passive"))
      (node (ref "DCM8") (pin "A") (pinfunction "A_A") (pintype "passive"))
      (node (ref "IC2") (pin "12") (pinfunction "C7_12") (pintype "bidirectional"))
      (node (ref "RCM7") (pin "2") (pinfunction "2_2") (pintype "passive"))
    )
    (net (code "34") (name "C8") (class "Default")
      (node (ref "L7") (pin "1") (pinfunction "1_1") (pintype "passive"))
      (node (ref "QB8") (pin "2") (pinfunction "S_2") (pintype "passive"))
      (node (ref "RCM8") (pin "1") (pinfunction "1_1") (pintype "passive"))
      (node (ref "X1") (pin "1") (pinfunction "S_1") (pintype "passive"))
    )
    (net (code "35") (name "C8M") (class "Default")
      (node (ref "CCM8") (pin "1") (pinfunction "1_1") (pintype "passive"))
      (node (ref "DCM8") (pin "C") (pinfunction "C_C") (pintype "passive"))
      (node (ref "IC2") (pin "10") (pinfunction "C8_10") (pintype "bidirectional"))
      (node (ref "IC2") (pin "2") (pinfunction "C12_2") (pintype "bidirectional"))
      (node (ref "IC2") (pin "4") (pinfunction "C11_4") (pintype "bidirectional"))
      (node (ref "IC2") (pin "6") (pinfunction "C10_6") (pintype "bidirectional"))
      (node (ref "IC2") (pin "8") (pinfunction "C9_8") (pintype "bidirectional"))
      (node (ref "RCM8") (pin "2") (pinfunction "2_2") (pintype "passive"))
    )
    (net (code "36") (name "CANH") (class "Default")
      (node (ref "L8") (pin "1") (pinfunction "1_1") (pintype "passive"))
      (node (ref "SJ1") (pin "2") (pinfunction "2_2") (pintype "passive"))
      (node (ref "X3") (pin "2") (pinfunction "S_2") (pintype "passive"))
    )
    (net (code "37") (name "CANL") (class "Default")
      (node (ref "L8") (pin "3") (pinfunction "3_3") (pintype "passive"))
      (node (ref "R22") (pin "2") (pinfunction "2_2") (pintype "passive"))
      (node (ref "X3") (pin "3") (pinfunction "S_3") (pintype "passive"))
    )
    (net (code "38") (name "CANRX") (class "Default")
      (node (ref "IC3") (pin "6") (pinfunction "O2_6") (pintype "bidirectional"))
      (node (ref "R7") (pin "2") (pinfunction "2_2") (pintype "passive"))
    )
    (net (code "39") (name "CANTX") (class "Default")
      (node (ref "IC3") (pin "7") (pinfunction "I1_7") (pintype "bidirectional"))
      (node (ref "R6") (pin "2") (pinfunction "2_2") (pintype "passive"))
    )
    (net (code "40") (name "CAR+12V") (class "Default")
      (node (ref "C3") (pin "1") (pinfunction "1_1") (pintype "passive"))
      (node (ref "L1") (pin "1") (pinfunction "1_1") (pintype "passive"))
      (node (ref "U1") (pin "3") (pinfunction "IN_3") (pintype "input"))
    )
    (net (code "41") (name "CAR+12VIN") (class "Default")
      (node (ref "C2") (pin "1") (pinfunction "1_1") (pintype "passive"))
      (node (ref "L1") (pin "2") (pinfunction "2_2") (pintype "passive"))
      (node (ref "X3") (pin "1") (pinfunction "S_1") (pintype "passive"))
    )
    (net (code "42") (name "CARGND") (class "Default")
      (node (ref "C16") (pin "2") (pinfunction "2_2") (pintype "passive"))
      (node (ref "C18") (pin "2") (pinfunction "2_2") (pintype "passive"))
      (node (ref "C19") (pin "2") (pinfunction "2_2") (pintype "passive"))
      (node (ref "C3") (pin "2") (pinfunction "2_2") (pintype "passive"))
      (node (ref "C6") (pin "2") (pinfunction "2_2") (pintype "passive"))
      (node (ref "C7") (pin "2") (pinfunction "2_2") (pintype "passive"))
      (node (ref "C8") (pin "2") (pinfunction "2_2") (pintype "passive"))
      (node (ref "DCDC1") (pin "1") (pinfunction "VIN-_1") (pintype "bidirectional"))
      (node (ref "IC3") (pin "4") (pinfunction "GND1_4") (pintype "bidirectional"))
      (node (ref "IC4") (pin "2") (pinfunction "VSS_2") (pintype "bidirectional"))
      (node (ref "L9") (pin "1") (pinfunction "1_1") (pintype "passive"))
      (node (ref "R12") (pin "2") (pinfunction "2_2") (pintype "passive"))
      (node (ref "U1") (pin "1") (pinfunction "ADJ_1") (pintype "input"))
    )
    (net (code "43") (name "CARGNDIN") (class "Default")
      (node (ref "C2") (pin "2") (pinfunction "2_2") (pintype "passive"))
      (node (ref "L9") (pin "2") (pinfunction "2_2") (pintype "passive"))
      (node (ref "X3") (pin "4") (pinfunction "S_4") (pintype "passive"))
    )
    (net (code "44") (name "CSB") (class "Default")
      (node (ref "IC2") (pin "44") (pinfunction "CSBI_44") (pintype "bidirectional"))
      (node (ref "R1") (pin "2") (pinfunction "2_2") (pintype "passive"))
      (node (ref "R20") (pin "1") (pinfunction "1_1") (pintype "passive"))
    )
    (net (code "45") (name "DBGEN") (class "Default")
      (node (ref "IC1") (pin "28") (pinfunction "PIO0_9/MOSI0/CT16B0_MAT1_28") (pintype "bidirectional"))
    )
    (net (code "46") (name "ERROR_LED") (class "Default")
      (node (ref "IC1") (pin "1") (pinfunction "PIO2_6_1") (pintype "bidirectional"))
    )
    (net (code "47") (name "FSM") (class "Default")
      (node (ref "CFSM") (pin "2") (pinfunction "2_2") (pintype "passive"))
      (node (ref "IC2") (pin "29") (pinfunction "VTEMP1_29") (pintype "bidirectional"))
      (node (ref "R10") (pin "1") (pinfunction "1_1") (pintype "passive"))
      (node (ref "R16") (pin "2") (pinfunction "2_2") (pintype "passive"))
    )
    (net (code "48") (name "GND") (class "Default")
      (node (ref "C1") (pin "2") (pinfunction "2_2") (pintype "passive"))
      (node (ref "C10") (pin "2") (pinfunction "2_2") (pintype "passive"))
      (node (ref "C11") (pin "2") (pinfunction "2_2") (pintype "passive"))
      (node (ref "C12") (pin "2") (pinfunction "2_2") (pintype "passive"))
      (node (ref "C13") (pin "2") (pinfunction "2_2") (pintype "passive"))
      (node (ref "C14") (pin "1") (pinfunction "1_1") (pintype "passive"))
      (node (ref "C15") (pin "1") (pinfunction "1_1") (pintype "passive"))
      (node (ref "C21") (pin "2") (pinfunction "2_2") (pintype "passive"))
      (node (ref "C22") (pin "2") (pinfunction "2_2") (pintype "passive"))
      (node (ref "C23") (pin "2") (pinfunction "2_2") (pintype "passive"))
      (node (ref "C24") (pin "2") (pinfunction "2_2") (pintype "passive"))
      (node (ref "C4") (pin "2") (pinfunction "2_2") (pintype "passive"))
      (node (ref "C5") (pin "2") (pinfunction "2_2") (pintype "passive"))
      (node (ref "C9") (pin "2") (pinfunction "2_2") (pintype "passive"))
      (node (ref "CFSM") (pin "1") (pinfunction "1_1") (pintype "passive"))
      (node (ref "CVREF") (pin "1") (pinfunction "1_1") (pintype "passive"))
      (node (ref "CVREG") (pin "1") (pinfunction "1_1") (pintype "passive"))
      (node (ref "D1") (pin "A") (pinfunction "A_A") (pintype "passive"))
      (node (ref "DCDC1") (pin "4") (pinfunction "VOUT-_4") (pintype "bidirectional"))
      (node (ref "IC1") (pin "41") (pinfunction "VSS_41") (pintype "bidirectional"))
      (node (ref "IC1") (pin "5") (pinfunction "VSS_5") (pintype "bidirectional"))
      (node (ref "IC2") (pin "27") (pinfunction "V-_27") (pintype "bidirectional"))
      (node (ref "IC2") (pin "33") (pinfunction "TOS_33") (pintype "bidirectional"))
      (node (ref "IC2") (pin "35") (pinfunction "GPIO1_35") (pintype "bidirectional"))
      (node (ref "IC2") (pin "36") (pinfunction "GPIO2_36") (pintype "bidirectional"))
      (node (ref "IC2") (pin "37") (pinfunction "A0_37") (pintype "bidirectional"))
      (node (ref "IC2") (pin "38") (pinfunction "A1_38") (pintype "bidirectional"))
      (node (ref "IC2") (pin "39") (pinfunction "A2_39") (pintype "bidirectional"))
      (node (ref "IC2") (pin "40") (pinfunction "A3_40") (pintype "bidirectional"))
      (node (ref "IC3") (pin "5") (pinfunction "GND2_5") (pintype "bidirectional"))
      (node (ref "JP2") (pin "6") (pinfunction "6_6") (pintype "passive"))
      (node (ref "NTC_C1") (pin "2") (pinfunction "2_2") (pintype "passive"))
      (node (ref "NTC_C2") (pin "2") (pinfunction "2_2") (pintype "passive"))
      (node (ref "Q2") (pin "2") (pinfunction "S_2") (pintype "passive"))
      (node (ref "Q3") (pin "2") (pinfunction "S_2") (pintype "passive"))
      (node (ref "R11") (pin "1") (pinfunction "1_1") (pintype "passive"))
      (node (ref "R16") (pin "1") (pinfunction "1_1") (pintype "passive"))
      (node (ref "RGQ1_3") (pin "1") (pinfunction "1_1") (pintype "passive"))
      (node (ref "V-R") (pin "2") (pinfunction "2_2") (pintype "passive"))
      (node (ref "X2") (pin "1") (pinfunction "S_1") (pintype "passive"))
      (node (ref "X2") (pin "3") (pinfunction "S_3") (pintype "passive"))
    )
    (net (code "49") (name "ISP_CAN") (class "Default")
      (node (ref "IC1") (pin "14") (pinfunction "PIO0_3_14") (pintype "bidirectional"))
      (node (ref "R11") (pin "2") (pinfunction "2_2") (pintype "passive"))
    )
    (net (code "50") (name "ISP_ENTER") (class "Default")
      (node (ref "IC1") (pin "4") (pinfunction "PIO0_1/CLKOUT/CT32B0_MAT2_4") (pintype "bidirectional"))
      (node (ref "JP2") (pin "5") (pinfunction "5_5") (pintype "passive"))
      (node (ref "R15") (pin "2") (pinfunction "2_2") (pintype "passive"))
    )
    (net (code "51") (name "Net-(C16-Pad1)") (class "Default")
      (node (ref "C16") (pin "1") (pinfunction "1_1") (pintype "passive"))
      (node (ref "R21") (pin "1") (pinfunction "1_1") (pintype "passive"))
      (node (ref "R22") (pin "1") (pinfunction "1_1") (pintype "passive"))
    )
    (net (code "52") (name "Net-(DCDC1-VIN+)") (class "Default")
      (node (ref "C19") (pin "1") (pinfunction "1_1") (pintype "passive"))
      (node (ref "DCDC1") (pin "2") (pinfunction "VIN+_2") (pintype "bidirectional"))
      (node (ref "L3") (pin "2") (pinfunction "2_2") (pintype "passive"))
      (node (ref "L4") (pin "2") (pinfunction "2_2") (pintype "passive"))
      (node (ref "U1") (pin "2") (pinfunction "OUT_2") (pintype "passive"))
      (node (ref "U1") (pin "4") (pinfunction "OUT_4") (pintype "passive"))
    )
    (net (code "53") (name "Net-(DCDC1-VOUT+)") (class "Default")
      (node (ref "C4") (pin "1") (pinfunction "1_1") (pintype "passive"))
      (node (ref "DCDC1") (pin "5") (pinfunction "VOUT+_5") (pintype "bidirectional"))
      (node (ref "L2") (pin "2") (pinfunction "2_2") (pintype "passive"))
    )
    (net (code "54") (name "Net-(IC1-CANRX)") (class "Default")
      (node (ref "IC1") (pin "19") (pinfunction "CANRX_19") (pintype "bidirectional"))
      (node (ref "R7") (pin "1") (pinfunction "1_1") (pintype "passive"))
    )
    (net (code "55") (name "Net-(IC1-CANTX)") (class "Default")
      (node (ref "IC1") (pin "20") (pinfunction "CANTX_20") (pintype "bidirectional"))
      (node (ref "R6") (pin "1") (pinfunction "1_1") (pintype "passive"))
    )
    (net (code "56") (name "Net-(IC1-PIO2_0{slash}~{DTR}{slash}SSEL1)") (class "Default")
      (node (ref "IC1") (pin "2") (pinfunction "PIO2_0/~{DTR}/SSEL1_2") (pintype "bidirectional"))
      (node (ref "R1") (pin "1") (pinfunction "1_1") (pintype "passive"))
    )
    (net (code "57") (name "Net-(IC1-PIO2_1{slash}~{DSR}{slash}SCK1)") (class "Default")
      (node (ref "IC1") (pin "13") (pinfunction "PIO2_1/~{DSR}/SCK1_13") (pintype "bidirectional"))
      (node (ref "R3") (pin "1") (pinfunction "1_1") (pintype "passive"))
    )
    (net (code "58") (name "Net-(IC1-PIO2_2{slash}~{DCD}{slash}MISO1)") (class "Default")
      (node (ref "IC1") (pin "26") (pinfunction "PIO2_2/~{DCD}/MISO1_26") (pintype "bidirectional"))
      (node (ref "R4") (pin "1") (pinfunction "1_1") (pintype "passive"))
    )
    (net (code "59") (name "Net-(IC1-PIO2_3{slash}~{RI}{slash}MOSI1)") (class "Default")
      (node (ref "IC1") (pin "38") (pinfunction "PIO2_3/~{RI}/MOSI1_38") (pintype "bidirectional"))
      (node (ref "R5") (pin "1") (pinfunction "1_1") (pintype "passive"))
    )
    (net (code "60") (name "Net-(IC1-XTALIN)") (class "Default")
      (node (ref "C15") (pin "2") (pinfunction "2_2") (pintype "passive"))
      (node (ref "IC1") (pin "6") (pinfunction "XTALIN_6") (pintype "bidirectional"))
      (node (ref "Y1") (pin "2") (pinfunction "2_2") (pintype "passive"))
    )
    (net (code "61") (name "Net-(IC1-XTALOUT)") (class "Default")
      (node (ref "C14") (pin "2") (pinfunction "2_2") (pintype "passive"))
      (node (ref "IC1") (pin "7") (pinfunction "XTALOUT_7") (pintype "bidirectional"))
      (node (ref "Y1") (pin "1") (pinfunction "1_1") (pintype "passive"))
    )
    (net (code "62") (name "Net-(IC2-WDTB)") (class "Default")
      (node (ref "IC2") (pin "34") (pinfunction "WDTB_34") (pintype "bidirectional"))
      (node (ref "R2") (pin "1") (pinfunction "1_1") (pintype "passive"))
    )
    (net (code "63") (name "Net-(IC3-I2)") (class "Default")
      (node (ref "IC3") (pin "3") (pinfunction "I2_3") (pintype "bidirectional"))
      (node (ref "R14") (pin "2") (pinfunction "2_2") (pintype "passive"))
    )
    (net (code "64") (name "Net-(IC3-O1)") (class "Default")
      (node (ref "IC3") (pin "2") (pinfunction "O1_2") (pintype "bidirectional"))
      (node (ref "R13") (pin "2") (pinfunction "2_2") (pintype "passive"))
    )
    (net (code "65") (name "Net-(IC3-VDD1)") (class "Default")
      (node (ref "C18") (pin "1") (pinfunction "1_1") (pintype "passive"))
      (node (ref "C8") (pin "1") (pinfunction "1_1") (pintype "passive"))
      (node (ref "IC3") (pin "1") (pinfunction "VDD1_1") (pintype "bidirectional"))
      (node (ref "L4") (pin "1") (pinfunction "1_1") (pintype "passive"))
    )
    (net (code "66") (name "Net-(IC3-VDD2)") (class "Default")
      (node (ref "C21") (pin "1") (pinfunction "1_1") (pintype "passive"))
      (node (ref "C9") (pin "1") (pinfunction "1_1") (pintype "passive"))
      (node (ref "IC3") (pin "8") (pinfunction "VDD2_8") (pintype "bidirectional"))
      (node (ref "L5") (pin "1") (pinfunction "1_1") (pintype "passive"))
    )
    (net (code "67") (name "Net-(IC4-CANH)") (class "Default")
      (node (ref "IC4") (pin "7") (pinfunction "CANH_7") (pintype "bidirectional"))
      (node (ref "L8") (pin "5") (pinfunction "2_5") (pintype "passive"))
    )
    (net (code "68") (name "Net-(IC4-CANL)") (class "Default")
      (node (ref "IC4") (pin "6") (pinfunction "CANL_6") (pintype "bidirectional"))
      (node (ref "L8") (pin "4") (pinfunction "4_4") (pintype "passive"))
    )
    (net (code "69") (name "Net-(IC4-RS)") (class "Default")
      (node (ref "IC4") (pin "8") (pinfunction "RS_8") (pintype "bidirectional"))
      (node (ref "R12") (pin "1") (pinfunction "1_1") (pintype "passive"))
    )
    (net (code "70") (name "Net-(IC4-RX)") (class "Default")
      (node (ref "IC4") (pin "4") (pinfunction "RX_4") (pintype "bidirectional"))
      (node (ref "R14") (pin "1") (pinfunction "1_1") (pintype "passive"))
    )
    (net (code "71") (name "Net-(IC4-TX)") (class "Default")
      (node (ref "IC4") (pin "1") (pinfunction "TX_1") (pintype "bidirectional"))
      (node (ref "R13") (pin "1") (pinfunction "1_1") (pintype "passive"))
    )
    (net (code "72") (name "Net-(IC4-VDD)") (class "Default")
      (node (ref "C6") (pin "1") (pinfunction "1_1") (pintype "passive"))
      (node (ref "C7") (pin "1") (pinfunction "1_1") (pintype "passive"))
      (node (ref "IC4") (pin "3") (pinfunction "VDD_3") (pintype "bidirectional"))
      (node (ref "L3") (pin "1") (pinfunction "1_1") (pintype "passive"))
    )
    (net (code "73") (name "Net-(L7-Pad2)") (class "Default")
      (node (ref "L7") (pin "2") (pinfunction "2_2") (pintype "passive"))
      (node (ref "V+R") (pin "1") (pinfunction "1_1") (pintype "passive"))
    )
    (net (code "74") (name "Net-(LED2-PadC)") (class "Default")
      (node (ref "LED2") (pin "C") (pinfunction "C_C") (pintype "passive"))
      (node (ref "R8") (pin "2") (pinfunction "2_2") (pintype "passive"))
    )
    (net (code "75") (name "Net-(Q1-G)") (class "Default")
      (node (ref "D2") (pin "A") (pinfunction "A_A") (pintype "passive"))
      (node (ref "Q1") (pin "1") (pinfunction "G_1") (pintype "passive"))
      (node (ref "RGQ1_1") (pin "2") (pinfunction "2_2") (pintype "passive"))
      (node (ref "RGQ1_2") (pin "2") (pinfunction "2_2") (pintype "passive"))
    )
    (net (code "76") (name "Net-(Q1-S)") (class "Default")
      (node (ref "D2") (pin "C") (pinfunction "C_C") (pintype "passive"))
      (node (ref "Q1") (pin "2") (pinfunction "S_2") (pintype "passive"))
      (node (ref "RGQ1_1") (pin "1") (pinfunction "1_1") (pintype "passive"))
      (node (ref "V+R") (pin "2") (pinfunction "2_2") (pintype "passive"))
    )
    (net (code "77") (name "Net-(Q2-D)") (class "Default")
      (node (ref "Q2") (pin "3") (pinfunction "D_3") (pintype "passive"))
      (node (ref "RGQ1_2") (pin "1") (pinfunction "1_1") (pintype "passive"))
    )
    (net (code "78") (name "Net-(Q3-D)") (class "Default")
      (node (ref "Q3") (pin "3") (pinfunction "D_3") (pintype "passive"))
      (node (ref "R8") (pin "1") (pinfunction "1_1") (pintype "passive"))
    )
    (net (code "79") (name "Net-(QB1-D)") (class "Default")
      (node (ref "QB1") (pin "3") (pinfunction "D_3") (pintype "passive"))
      (node (ref "RP1") (pin "2") (pinfunction "2_2") (pintype "passive"))
    )
    (net (code "80") (name "Net-(QB1-G)") (class "Default")
      (node (ref "QB1") (pin "1") (pinfunction "G_1") (pintype "passive"))
      (node (ref "RBG1") (pin "1") (pinfunction "1_1") (pintype "passive"))
    )
    (net (code "81") (name "Net-(QB2-D)") (class "Default")
      (node (ref "QB2") (pin "3") (pinfunction "D_3") (pintype "passive"))
      (node (ref "RP2") (pin "2") (pinfunction "2_2") (pintype "passive"))
    )
    (net (code "82") (name "Net-(QB2-G)") (class "Default")
      (node (ref "QB2") (pin "1") (pinfunction "G_1") (pintype "passive"))
      (node (ref "RBG2") (pin "1") (pinfunction "1_1") (pintype "passive"))
    )
    (net (code "83") (name "Net-(QB3-D)") (class "Default")
      (node (ref "QB3") (pin "3") (pinfunction "D_3") (pintype "passive"))
      (node (ref "RP3") (pin "2") (pinfunction "2_2") (pintype "passive"))
    )
    (net (code "84") (name "Net-(QB3-G)") (class "Default")
      (node (ref "QB3") (pin "1") (pinfunction "G_1") (pintype "passive"))
      (node (ref "RBG3") (pin "1") (pinfunction "1_1") (pintype "passive"))
    )
    (net (code "85") (name "Net-(QB4-D)") (class "Default")
      (node (ref "QB4") (pin "3") (pinfunction "D_3") (pintype "passive"))
      (node (ref "RP4") (pin "2") (pinfunction "2_2") (pintype "passive"))
    )
    (net (code "86") (name "Net-(QB4-G)") (class "Default")
      (node (ref "QB4") (pin "1") (pinfunction "G_1") (pintype "passive"))
      (node (ref "RBG4") (pin "1") (pinfunction "1_1") (pintype "passive"))
    )
    (net (code "87") (name "Net-(QB5-D)") (class "Default")
      (node (ref "QB5") (pin "3") (pinfunction "D_3") (pintype "passive"))
      (node (ref "RP5") (pin "2") (pinfunction "2_2") (pintype "passive"))
    )
    (net (code "88") (name "Net-(QB5-G)") (class "Default")
      (node (ref "QB5") (pin "1") (pinfunction "G_1") (pintype "passive"))
      (node (ref "RBG5") (pin "1") (pinfunction "1_1") (pintype "passive"))
    )
    (net (code "89") (name "Net-(QB6-D)") (class "Default")
      (node (ref "QB6") (pin "3") (pinfunction "D_3") (pintype "passive"))
      (node (ref "RP6") (pin "2") (pinfunction "2_2") (pintype "passive"))
    )
    (net (code "90") (name "Net-(QB6-G)") (class "Default")
      (node (ref "QB6") (pin "1") (pinfunction "G_1") (pintype "passive"))
      (node (ref "RBG6") (pin "1") (pinfunction "1_1") (pintype "passive"))
    )
    (net (code "91") (name "Net-(QB7-D)") (class "Default")
      (node (ref "QB7") (pin "3") (pinfunction "D_3") (pintype "passive"))
      (node (ref "RP7") (pin "2") (pinfunction "2_2") (pintype "passive"))
    )
    (net (code "92") (name "Net-(QB7-G)") (class "Default")
      (node (ref "QB7") (pin "1") (pinfunction "G_1") (pintype "passive"))
      (node (ref "RBG7") (pin "1") (pinfunction "1_1") (pintype "passive"))
    )
    (net (code "93") (name "Net-(QB8-D)") (class "Default")
      (node (ref "QB8") (pin "3") (pinfunction "D_3") (pintype "passive"))
      (node (ref "RP8") (pin "2") (pinfunction "2_2") (pintype "passive"))
    )
    (net (code "94") (name "Net-(QB8-G)") (class "Default")
      (node (ref "QB8") (pin "1") (pinfunction "G_1") (pintype "passive"))
      (node (ref "RBG8") (pin "1") (pinfunction "1_1") (pintype "passive"))
    )
    (net (code "95") (name "Net-(R21-Pad2)") (class "Default")
      (node (ref "R21") (pin "2") (pinfunction "2_2") (pintype "passive"))
      (node (ref "SJ1") (pin "1") (pinfunction "1_1") (pintype "passive"))
    )
    (net (code "96") (name "SCK") (class "Default")
      (node (ref "IC2") (pin "41") (pinfunction "SCKI_41") (pintype "bidirectional"))
      (node (ref "R17") (pin "1") (pinfunction "1_1") (pintype "passive"))
      (node (ref "R3") (pin "2") (pinfunction "2_2") (pintype "passive"))
    )
    (net (code "97") (name "SDI") (class "Default")
      (node (ref "IC2") (pin "42") (pinfunction "SDI_42") (pintype "bidirectional"))
      (node (ref "R18") (pin "1") (pinfunction "1_1") (pintype "passive"))
      (node (ref "R5") (pin "2") (pinfunction "2_2") (pintype "passive"))
    )
    (net (code "98") (name "SDO") (class "Default")
      (node (ref "IC2") (pin "43") (pinfunction "SDO_43") (pintype "bidirectional"))
      (node (ref "R19") (pin "1") (pinfunction "1_1") (pintype "passive"))
      (node (ref "R4") (pin "2") (pinfunction "2_2") (pintype "passive"))
    )
    (net (code "99") (name "SWCLK") (class "Default")
      (node (ref "IC1") (pin "29") (pinfunction "PIO0_10/SWCLK/SCK0/CT16B0_MAT2_29") (pintype "bidirectional"))
      (node (ref "JP2") (pin "4") (pinfunction "4_4") (pintype "passive"))
    )
    (net (code "100") (name "SWDIO") (class "Default")
      (node (ref "IC1") (pin "39") (pinfunction "PIO1_3/SWDIO/AD4/CT32B1_MAT2_39") (pintype "bidirectional"))
      (node (ref "JP2") (pin "3") (pinfunction "3_3") (pintype "passive"))
    )
    (net (code "101") (name "V+") (class "Default")
      (node (ref "C1") (pin "1") (pinfunction "1_1") (pintype "passive"))
      (node (ref "D1") (pin "C") (pinfunction "C_C") (pintype "passive"))
      (node (ref "IC2") (pin "1") (pinfunction "V+_1") (pintype "bidirectional"))
      (node (ref "Q1") (pin "3") (pinfunction "D_3") (pintype "passive"))
      (node (ref "R10") (pin "2") (pinfunction "2_2") (pintype "passive"))
    )
    (net (code "102") (name "VREF") (class "Default")
      (node (ref "CVREF") (pin "2") (pinfunction "2_2") (pintype "passive"))
      (node (ref "IC2") (pin "31") (pinfunction "VREF_31") (pintype "bidirectional"))
    )
    (net (code "103") (name "VREG") (class "Default")
      (node (ref "CVREG") (pin "2") (pinfunction "2_2") (pintype "passive"))
      (node (ref "IC2") (pin "32") (pinfunction "VREG_32") (pintype "bidirectional"))
      (node (ref "R17") (pin "2") (pinfunction "2_2") (pintype "passive"))
      (node (ref "R18") (pin "2") (pinfunction "2_2") (pintype "passive"))
      (node (ref "R19") (pin "2") (pinfunction "2_2") (pintype "passive"))
      (node (ref "R2") (pin "2") (pinfunction "2_2") (pintype "passive"))
      (node (ref "R20") (pin "2") (pinfunction "2_2") (pintype "passive"))
    )
    (net (code "104") (name "unconnected-(IC1-PIO0_2{slash}SSEL{slash}CT16B0_CAP0-Pad10)") (class "Default")
      (node (ref "IC1") (pin "10") (pinfunction "PIO0_2/SSEL/CT16B0_CAP0_10") (pintype "bidirectional"))
    )
    (net (code "105") (name "unconnected-(IC1-PIO0_4{slash}SCL-Pad15)") (class "Default")
      (node (ref "IC1") (pin "15") (pinfunction "PIO0_4/SCL_15") (pintype "bidirectional"))
    )
    (net (code "106") (name "unconnected-(IC1-PIO0_5{slash}SDA-Pad16)") (class "Default")
      (node (ref "IC1") (pin "16") (pinfunction "PIO0_5/SDA_16") (pintype "bidirectional"))
    )
    (net (code "107") (name "unconnected-(IC1-PIO0_6{slash}SCK0-Pad22)") (class "Default")
      (node (ref "IC1") (pin "22") (pinfunction "PIO0_6/SCK0_22") (pintype "bidirectional"))
    )
    (net (code "108") (name "unconnected-(IC1-PIO0_7{slash}~{CTS}-Pad23)") (class "Default")
      (node (ref "IC1") (pin "23") (pinfunction "PIO0_7/~{CTS}_23") (pintype "bidirectional"))
    )
    (net (code "109") (name "unconnected-(IC1-PIO0_8{slash}MISO0{slash}CT16B0_MAT0-Pad27)") (class "Default")
      (node (ref "IC1") (pin "27") (pinfunction "PIO0_8/MISO0/CT16B0_MAT0_27") (pintype "bidirectional"))
    )
    (net (code "110") (name "unconnected-(IC1-PIO1_5{slash}~{RTS}{slash}CT32B0_CAP0-Pad45)") (class "Default")
      (node (ref "IC1") (pin "45") (pinfunction "PIO1_5/~{RTS}/CT32B0_CAP0_45") (pintype "bidirectional"))
    )
    (net (code "111") (name "unconnected-(IC1-PIO1_6{slash}RXD{slash}CT32B0_MAT0-Pad46)") (class "Default")
      (node (ref "IC1") (pin "46") (pinfunction "PIO1_6/RXD/CT32B0_MAT0_46") (pintype "bidirectional"))
    )
    (net (code "112") (name "unconnected-(IC1-PIO1_7{slash}TXD{slash}CT32B0_MAT1-Pad47)") (class "Default")
      (node (ref "IC1") (pin "47") (pinfunction "PIO1_7/TXD/CT32B0_MAT1_47") (pintype "bidirectional"))
    )
    (net (code "113") (name "unconnected-(IC1-PIO1_8{slash}CT16B1_CAP0-Pad9)") (class "Default")
      (node (ref "IC1") (pin "9") (pinfunction "PIO1_8/CT16B1_CAP0_9") (pintype "bidirectional"))
    )
    (net (code "114") (name "unconnected-(IC1-PIO1_9{slash}CT16B1_MAT0-Pad17)") (class "Default")
      (node (ref "IC1") (pin "17") (pinfunction "PIO1_9/CT16B1_MAT0_17") (pintype "bidirectional"))
    )
    (net (code "115") (name "unconnected-(IC1-PIO2_4-Pad18)") (class "Default")
      (node (ref "IC1") (pin "18") (pinfunction "PIO2_4_18") (pintype "bidirectional"))
    )
    (net (code "116") (name "unconnected-(IC1-PIO2_5-Pad21)") (class "Default")
      (node (ref "IC1") (pin "21") (pinfunction "PIO2_5_21") (pintype "bidirectional"))
    )
    (net (code "117") (name "unconnected-(IC1-PIO2_7-Pad11)") (class "Default")
      (node (ref "IC1") (pin "11") (pinfunction "PIO2_7_11") (pintype "bidirectional"))
    )
    (net (code "118") (name "unconnected-(IC1-PIO2_8-Pad12)") (class "Default")
      (node (ref "IC1") (pin "12") (pinfunction "PIO2_8_12") (pintype "bidirectional"))
    )
    (net (code "119") (name "unconnected-(IC1-PIO2_9-Pad24)") (class "Default")
      (node (ref "IC1") (pin "24") (pinfunction "PIO2_9_24") (pintype "bidirectional"))
    )
    (net (code "120") (name "unconnected-(IC1-PIO2_10-Pad25)") (class "Default")
      (node (ref "IC1") (pin "25") (pinfunction "PIO2_10_25") (pintype "bidirectional"))
    )
    (net (code "121") (name "unconnected-(IC1-PIO2_11{slash}SCK0-Pad31)") (class "Default")
      (node (ref "IC1") (pin "31") (pinfunction "PIO2_11/SCK0_31") (pintype "bidirectional"))
    )
    (net (code "122") (name "unconnected-(IC1-PIO3_0{slash}~{DTR}-Pad36)") (class "Default")
      (node (ref "IC1") (pin "36") (pinfunction "PIO3_0/~{DTR}_36") (pintype "bidirectional"))
    )
    (net (code "123") (name "unconnected-(IC1-PIO3_1{slash}~{DSR}-Pad37)") (class "Default")
      (node (ref "IC1") (pin "37") (pinfunction "PIO3_1/~{DSR}_37") (pintype "bidirectional"))
    )
    (net (code "124") (name "unconnected-(IC1-PIO3_2{slash}~{DCD}-Pad43)") (class "Default")
      (node (ref "IC1") (pin "43") (pinfunction "PIO3_2/~{DCD}_43") (pintype "bidirectional"))
    )
    (net (code "125") (name "unconnected-(IC2-S9-Pad9)") (class "Default")
      (node (ref "IC2") (pin "9") (pinfunction "S9_9") (pintype "bidirectional"))
    )
    (net (code "126") (name "unconnected-(IC2-S10-Pad7)") (class "Default")
      (node (ref "IC2") (pin "7") (pinfunction "S10_7") (pintype "bidirectional"))
    )
    (net (code "127") (name "unconnected-(IC2-S11-Pad5)") (class "Default")
      (node (ref "IC2") (pin "5") (pinfunction "S11_5") (pintype "bidirectional"))
    )
    (net (code "128") (name "unconnected-(IC2-S12-Pad3)") (class "Default")
      (node (ref "IC2") (pin "3") (pinfunction "S12_3") (pintype "bidirectional"))
    )
    (net (code "129") (name "unconnected-(IC4-VRF-Pad5)") (class "Default")
      (node (ref "IC4") (pin "5") (pinfunction "VRF_5") (pintype "bidirectional"))
    )
    (net (code "130") (name "~{RESET}") (class "Default")
      (node (ref "C24") (pin "1") (pinfunction "1_1") (pintype "passive"))
      (node (ref "IC1") (pin "3") (pinfunction "PIO0_0/~{RESET}_3") (pintype "bidirectional"))
      (node (ref "JP2") (pin "1") (pinfunction "1_1") (pintype "passive"))
      (node (ref "R9") (pin "2") (pinfunction "2_2") (pintype "passive"))
    )
  )
)
